# FY.net
KiCad netlist of a schematic drawn in EAGLE
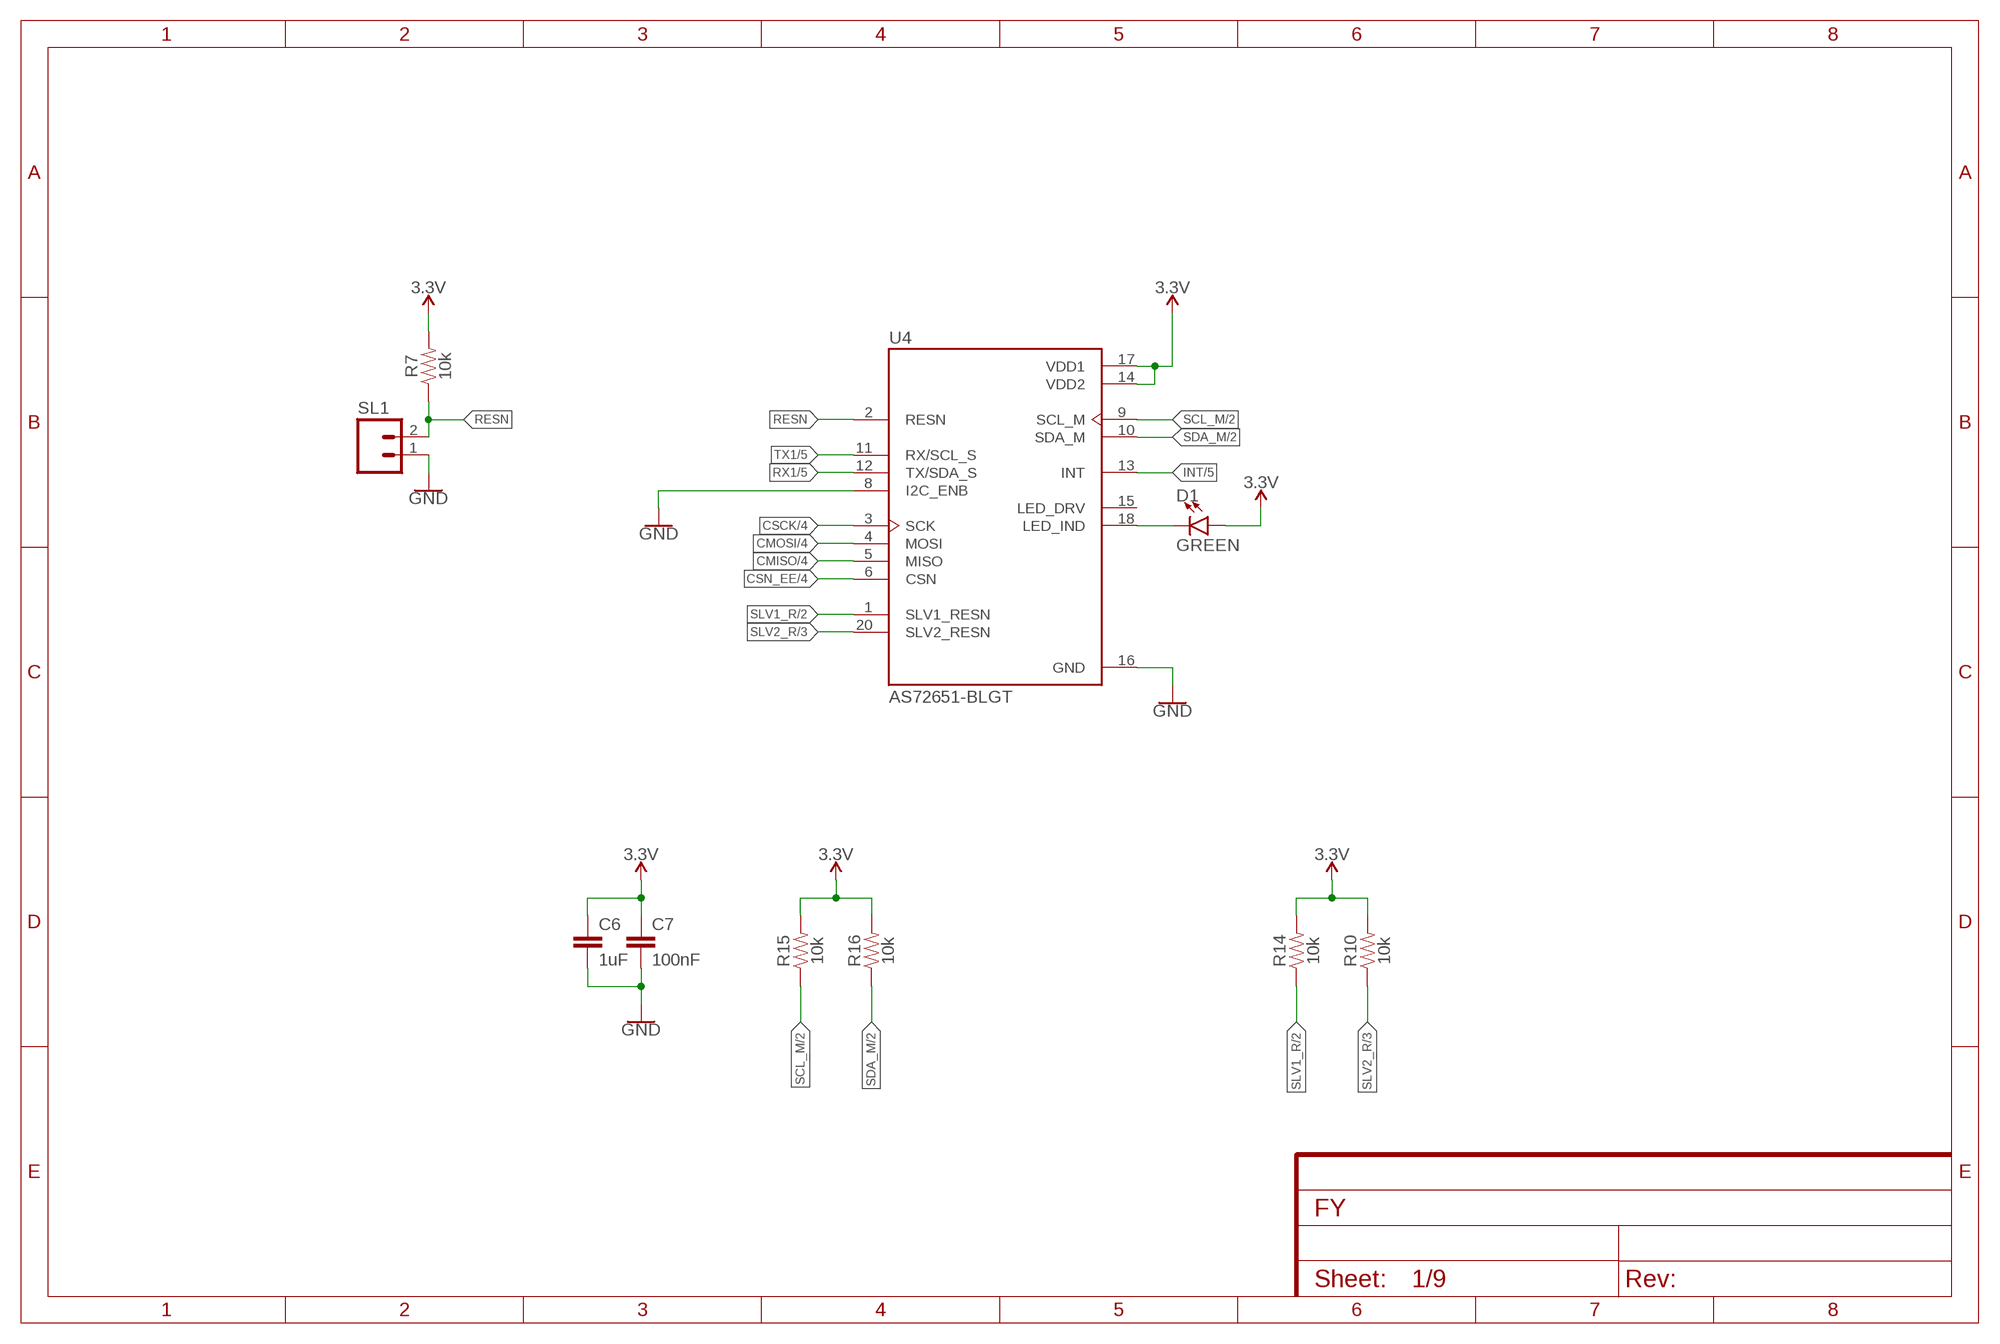
[diagram p0: schematic, sheet 1]
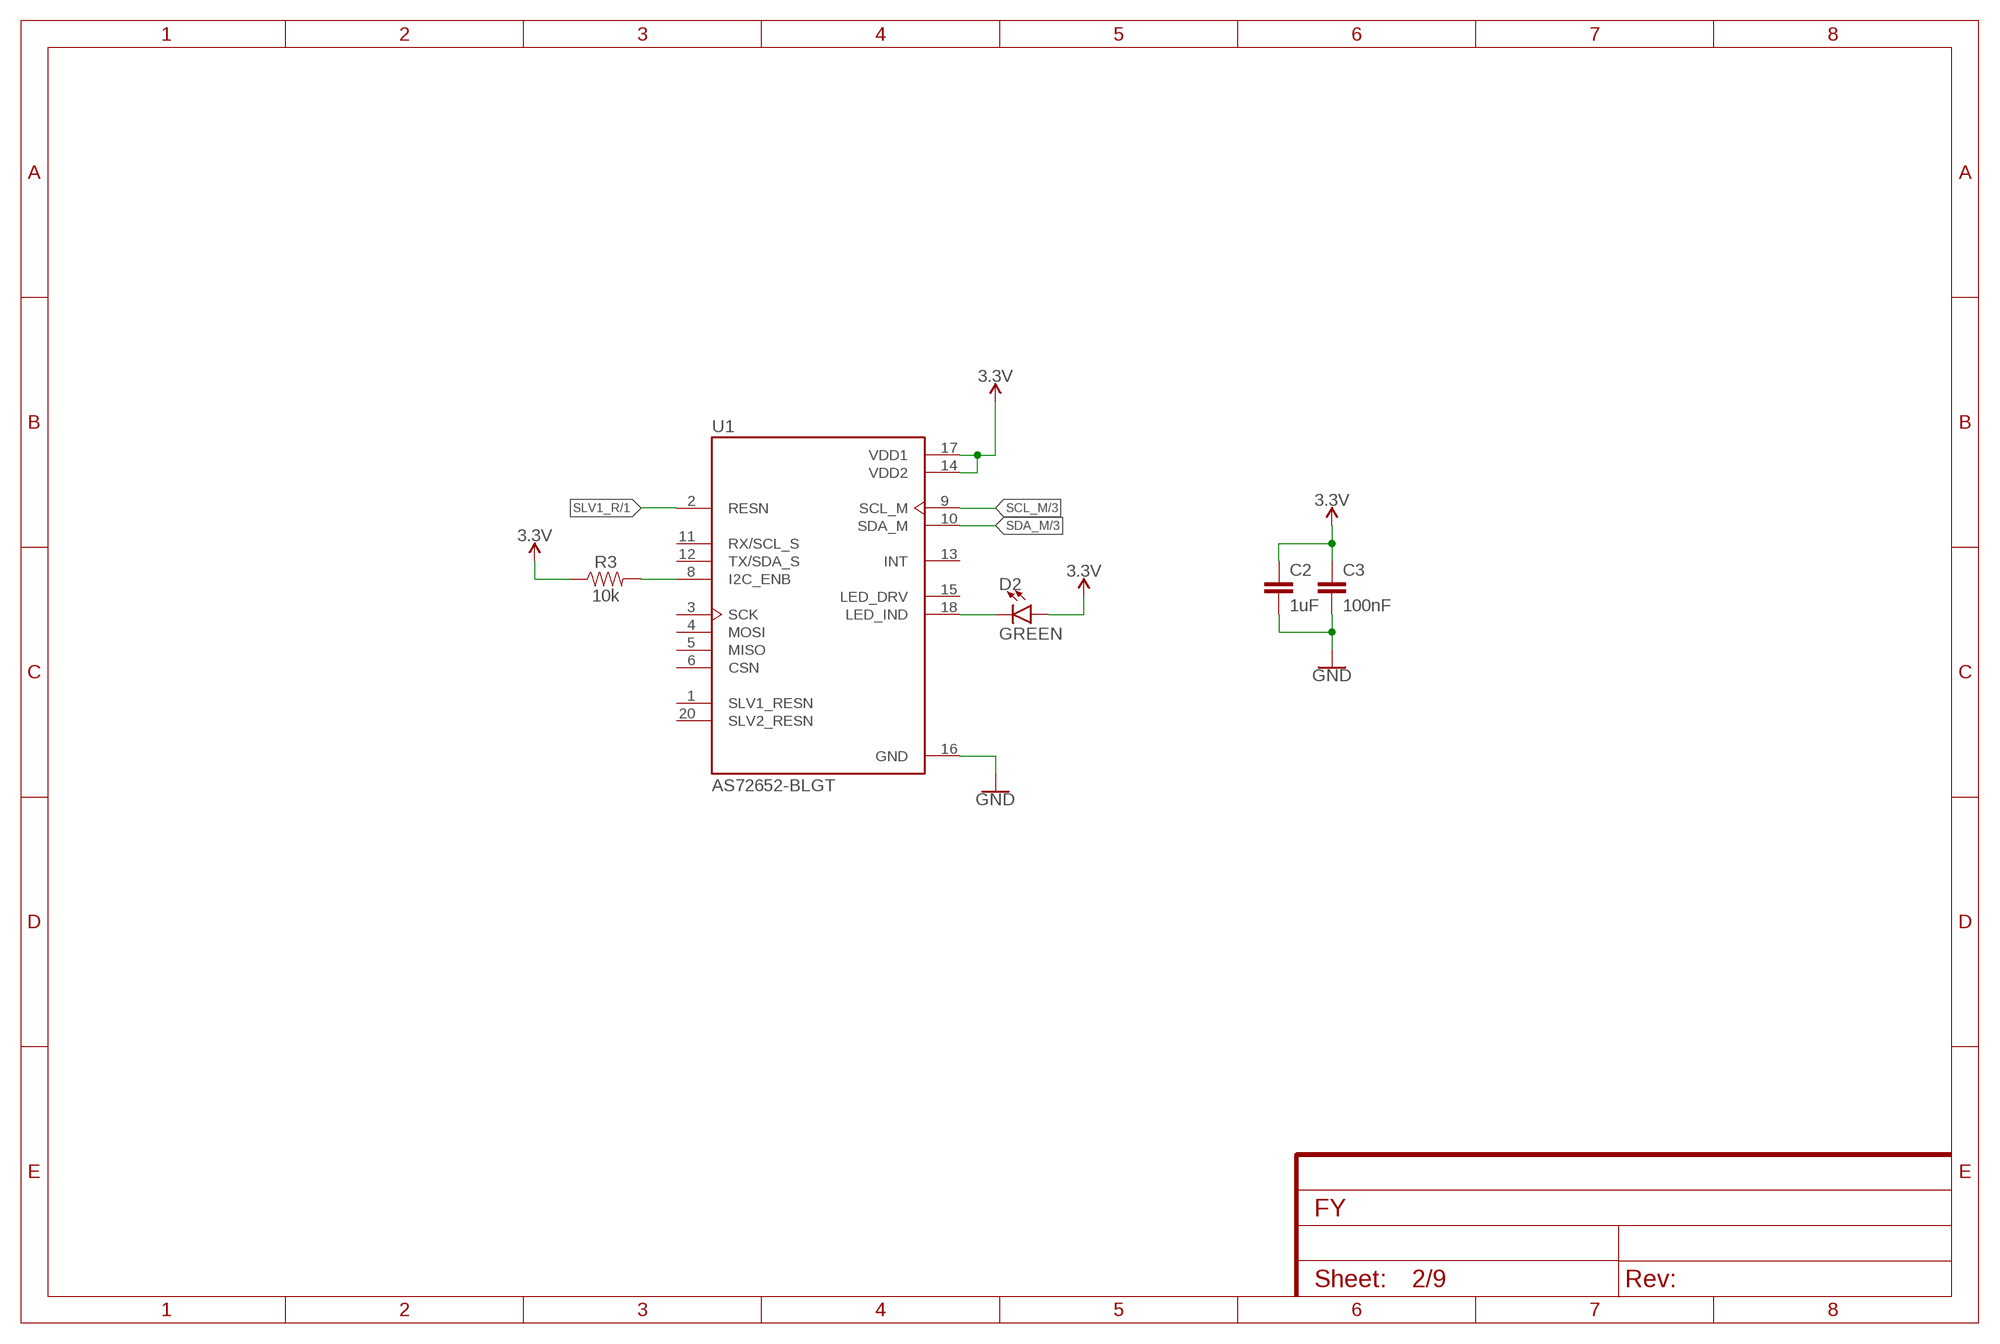
[diagram p1: schematic, sheet 2]
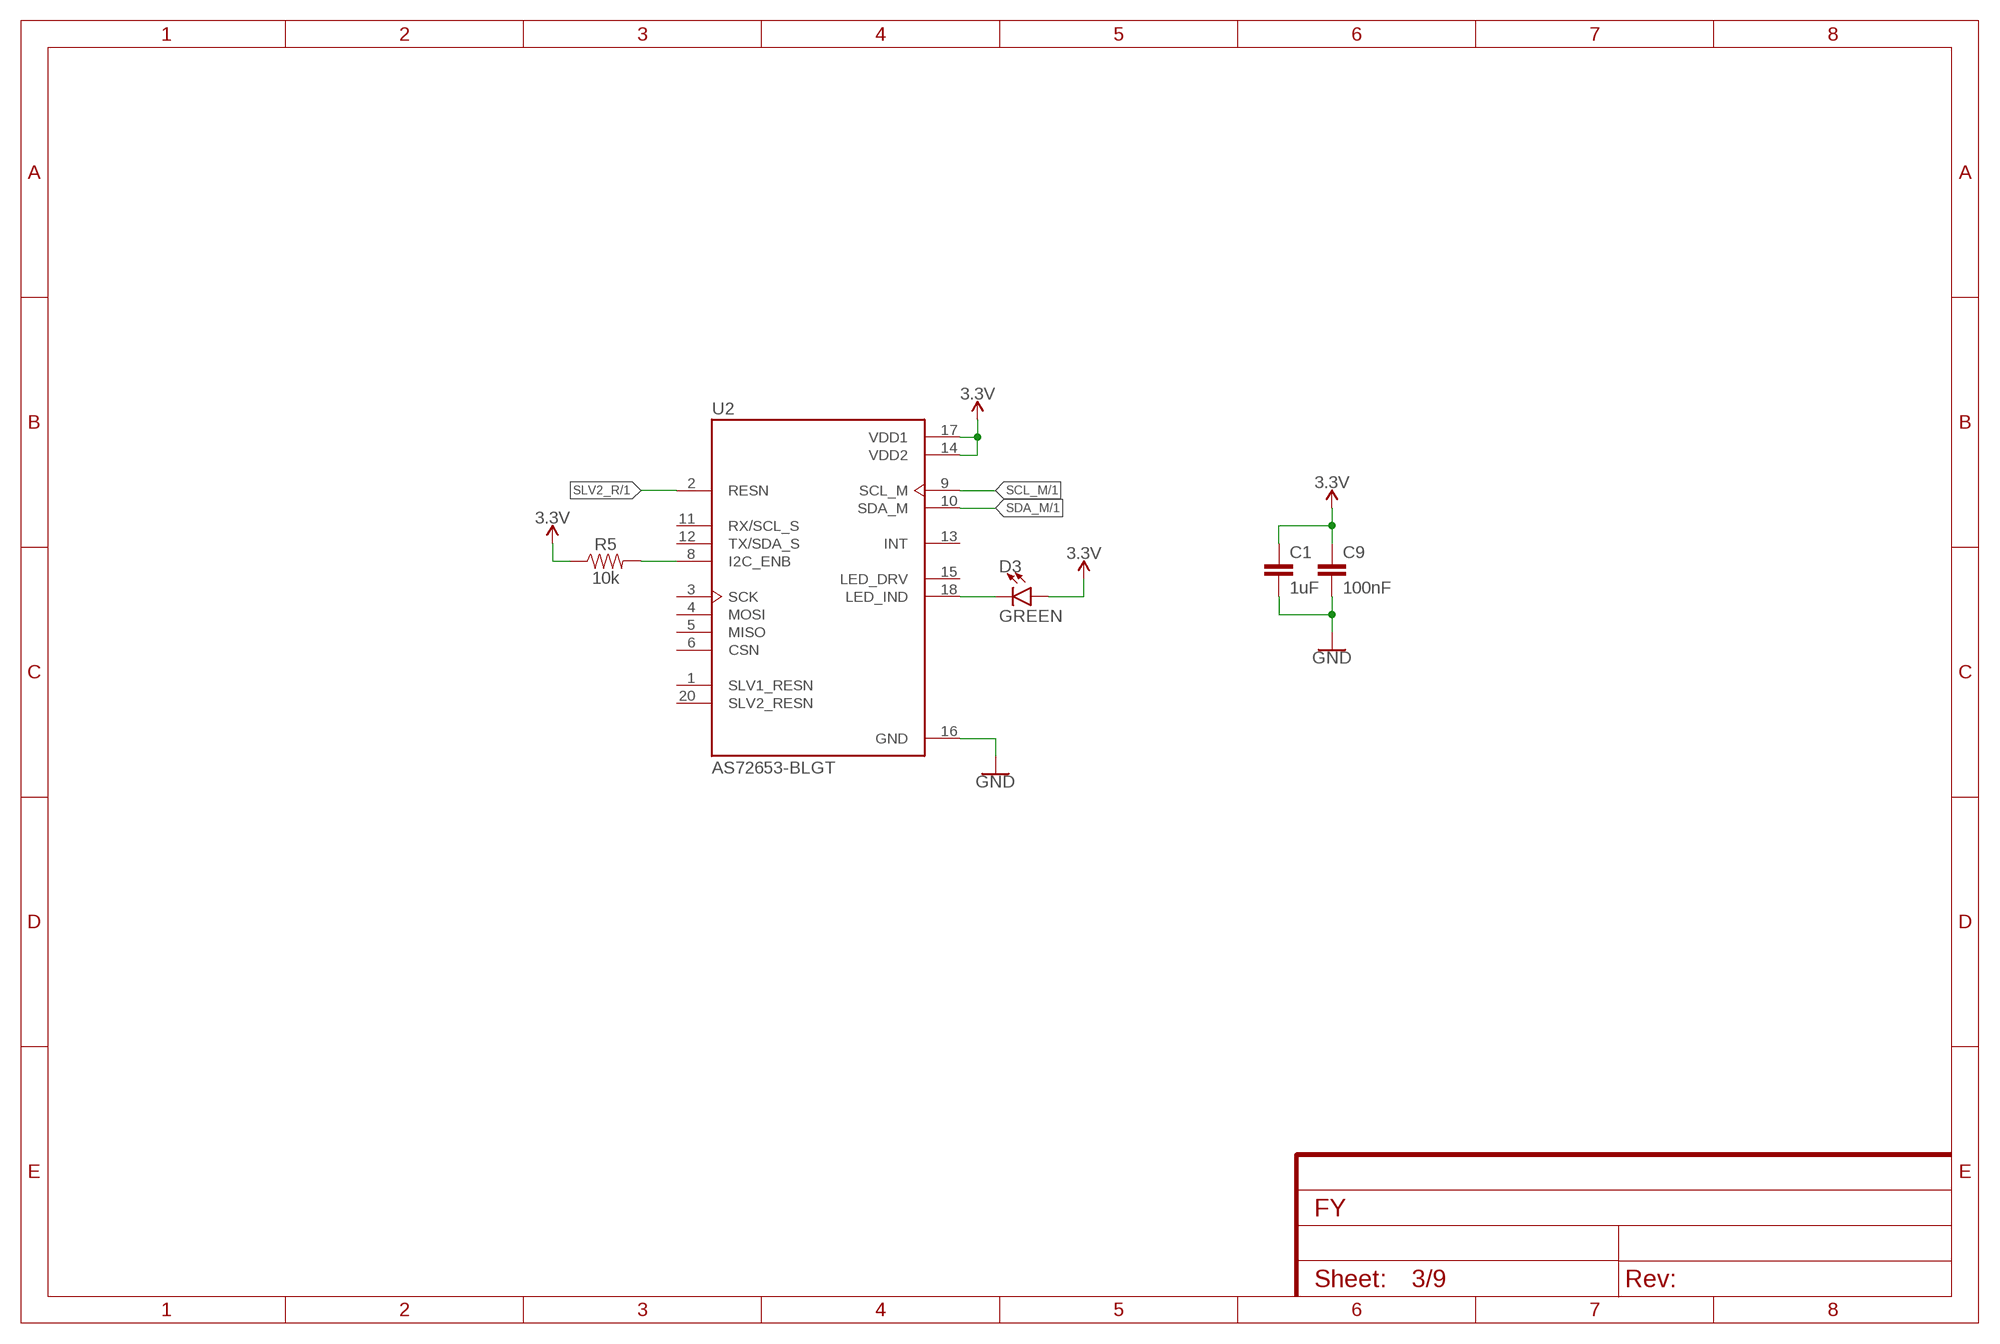
[diagram p2: schematic, sheet 3]
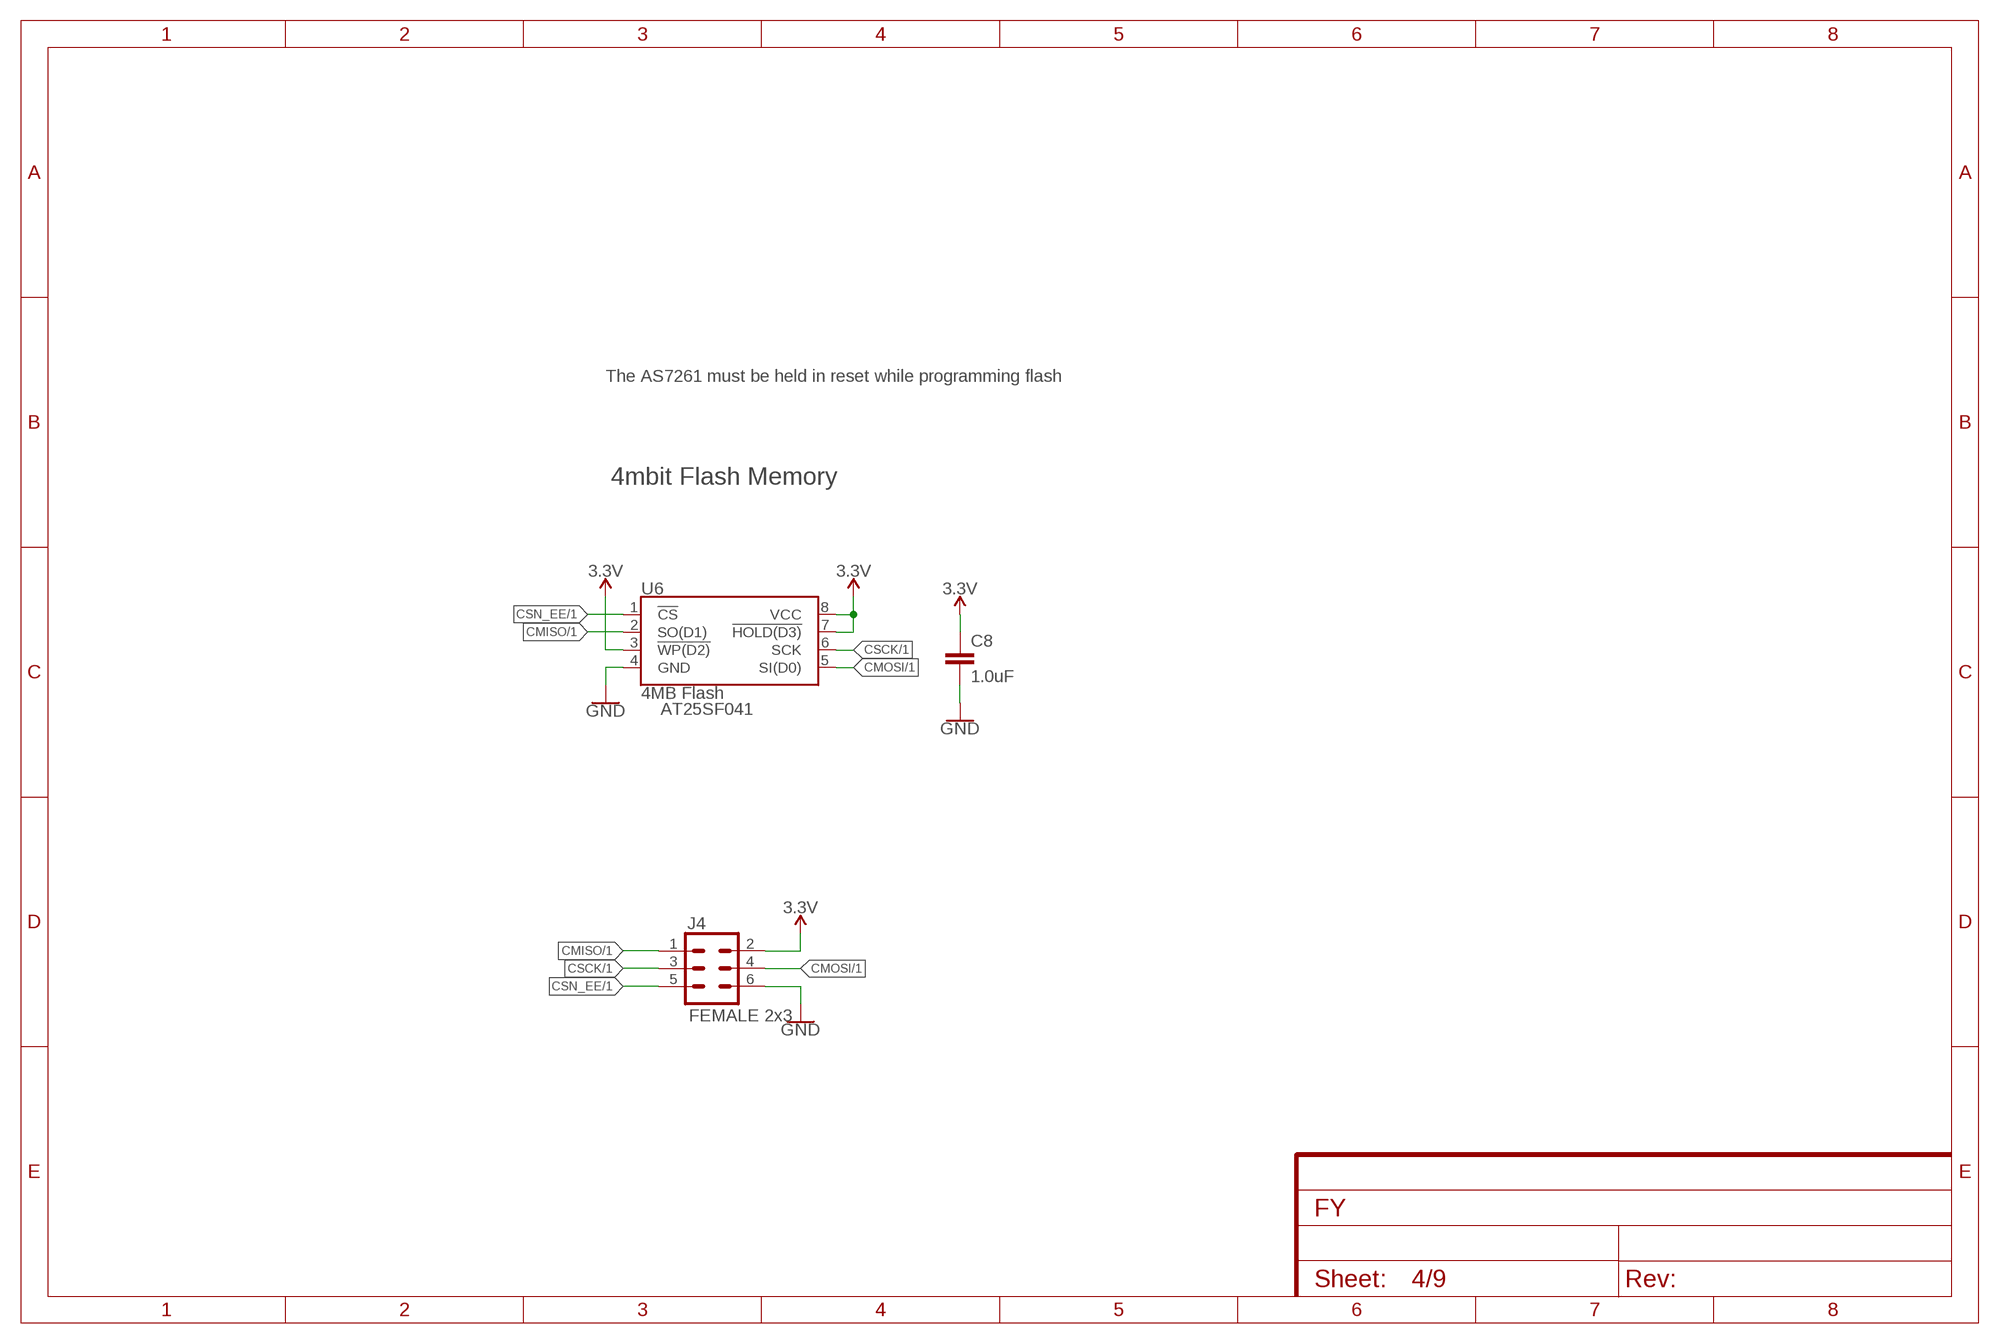
[diagram p3: schematic, sheet 4]
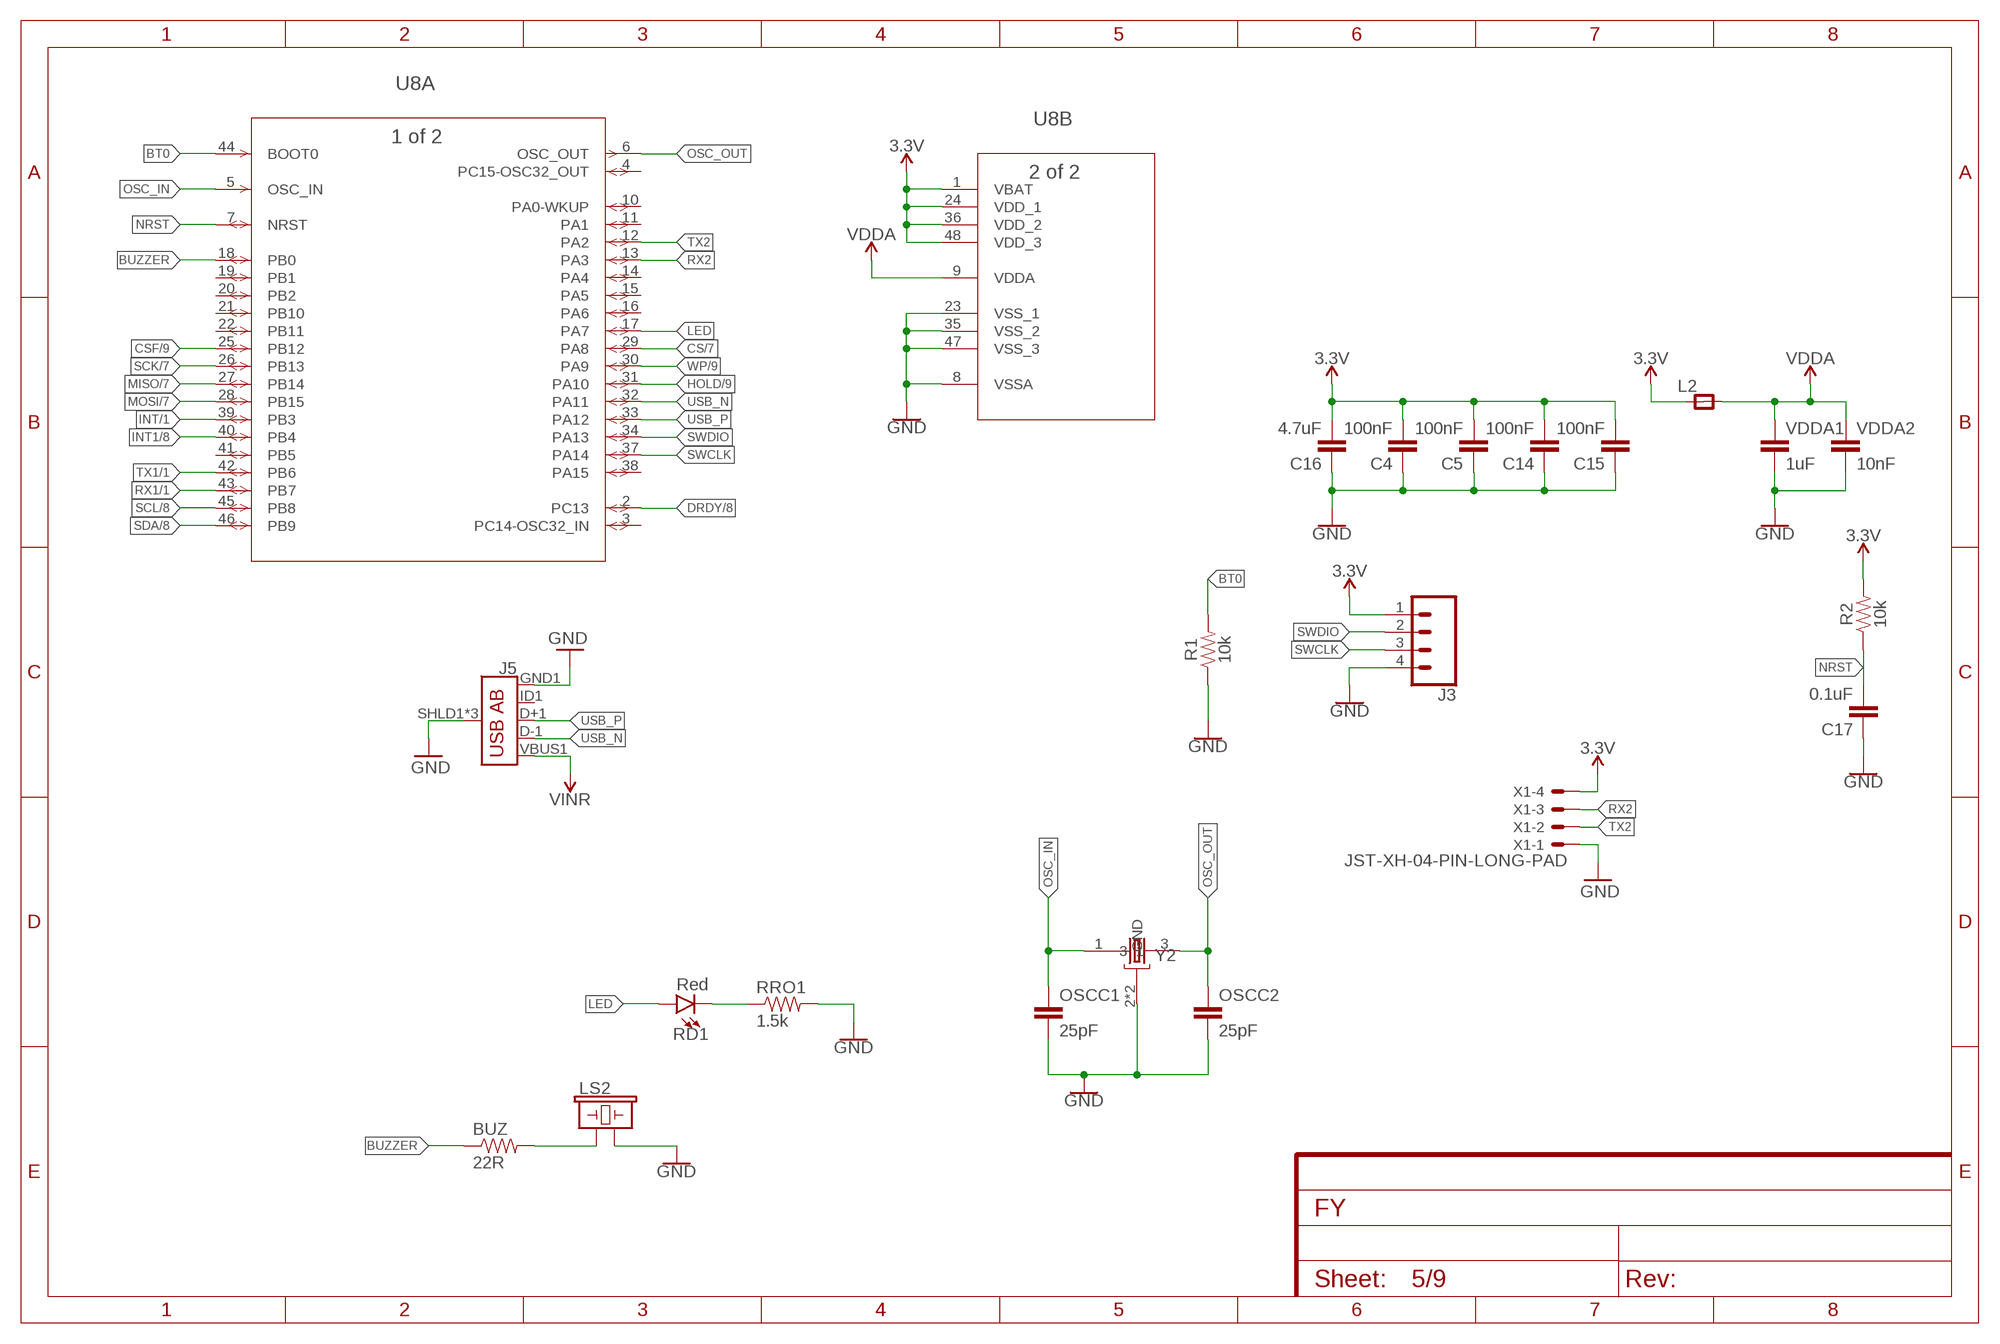
[diagram p4: schematic, sheet 5]
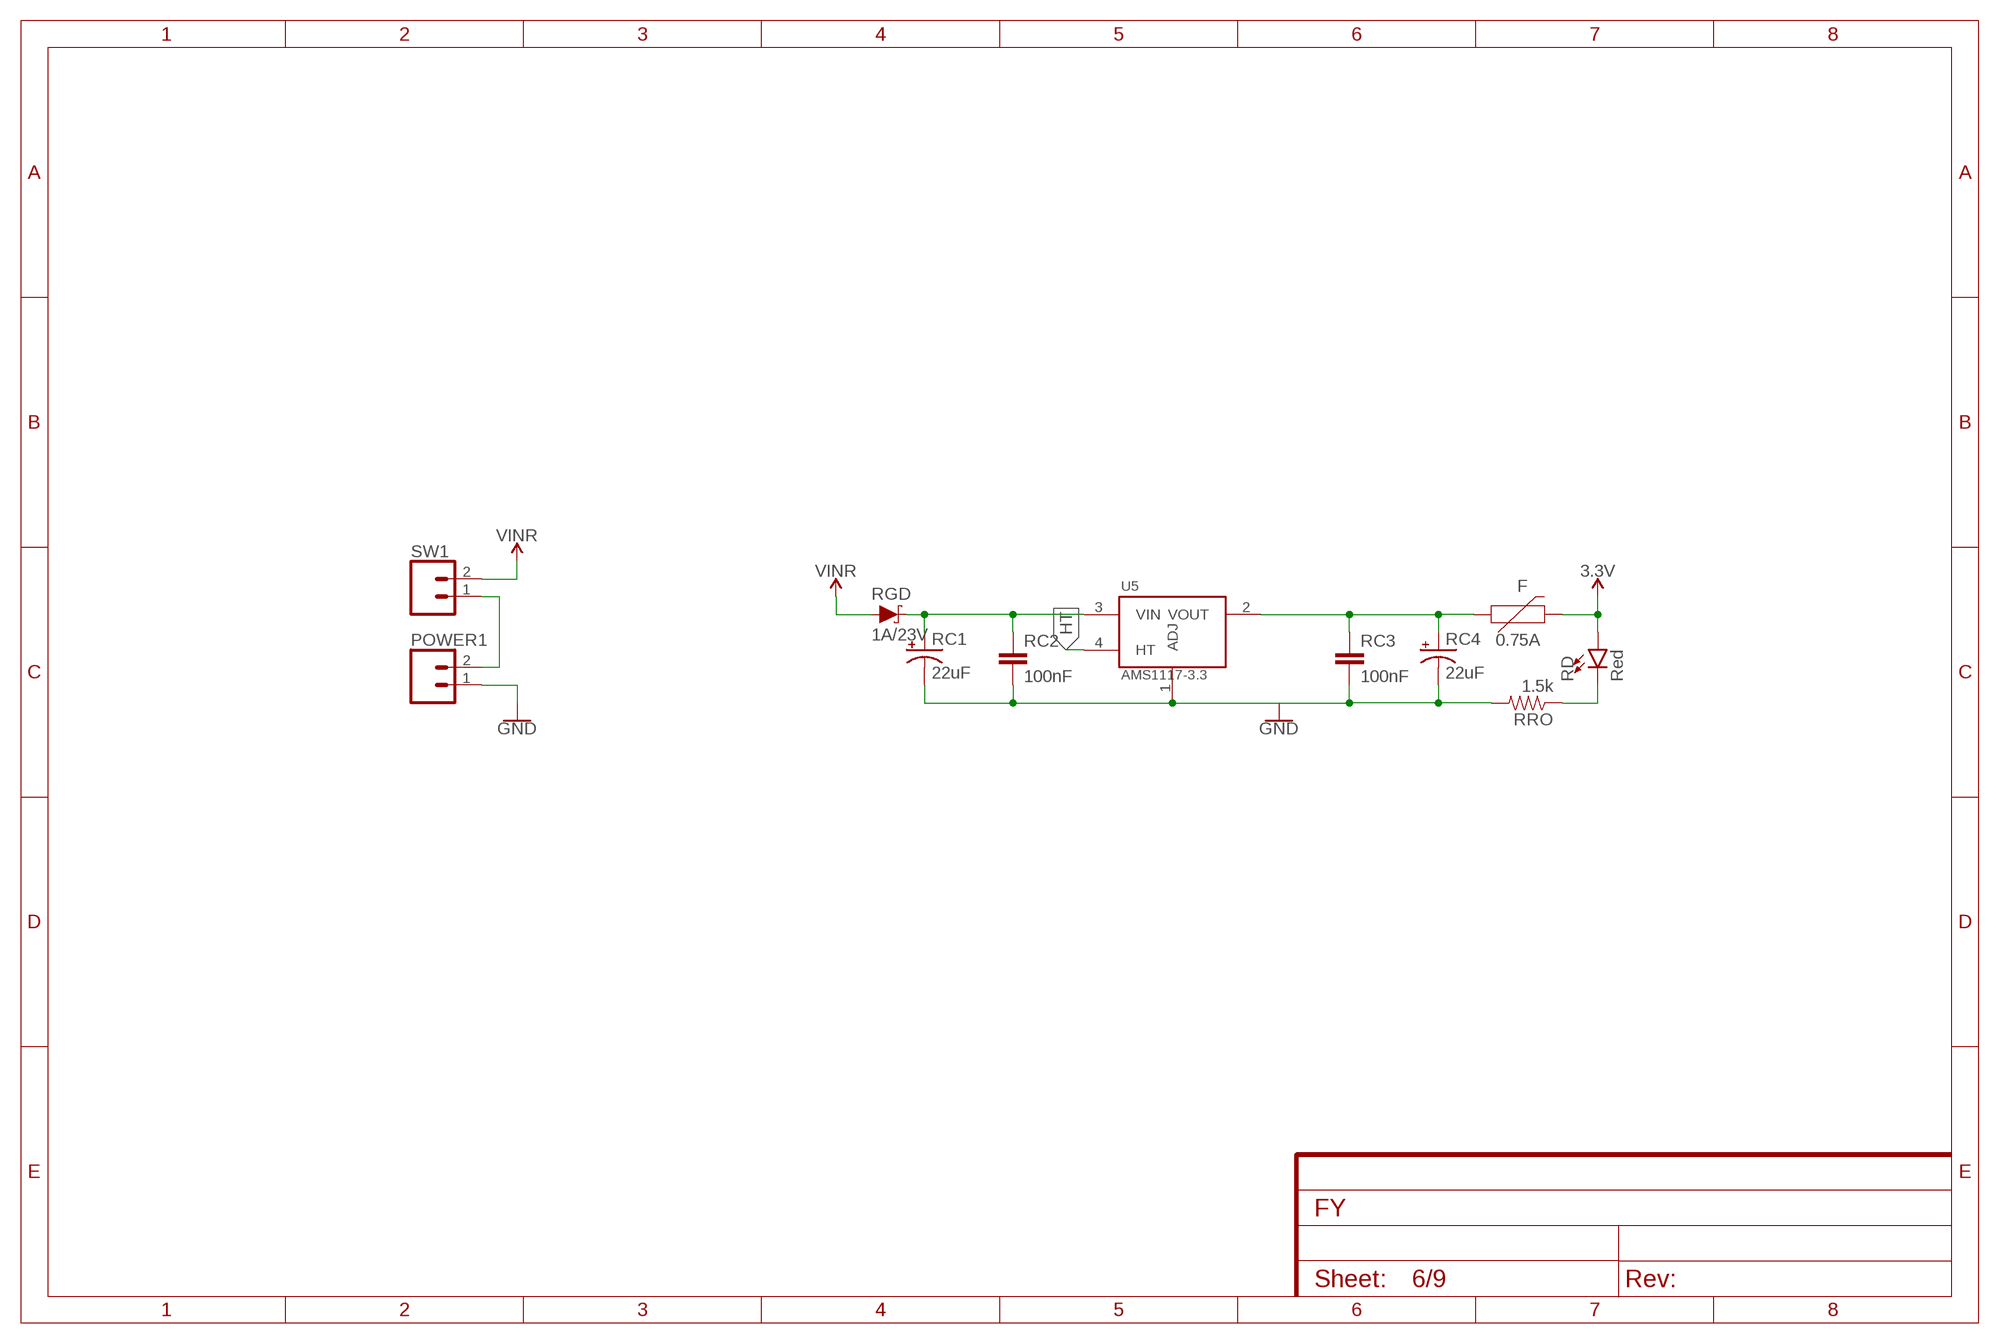
[diagram p5: schematic, sheet 6]
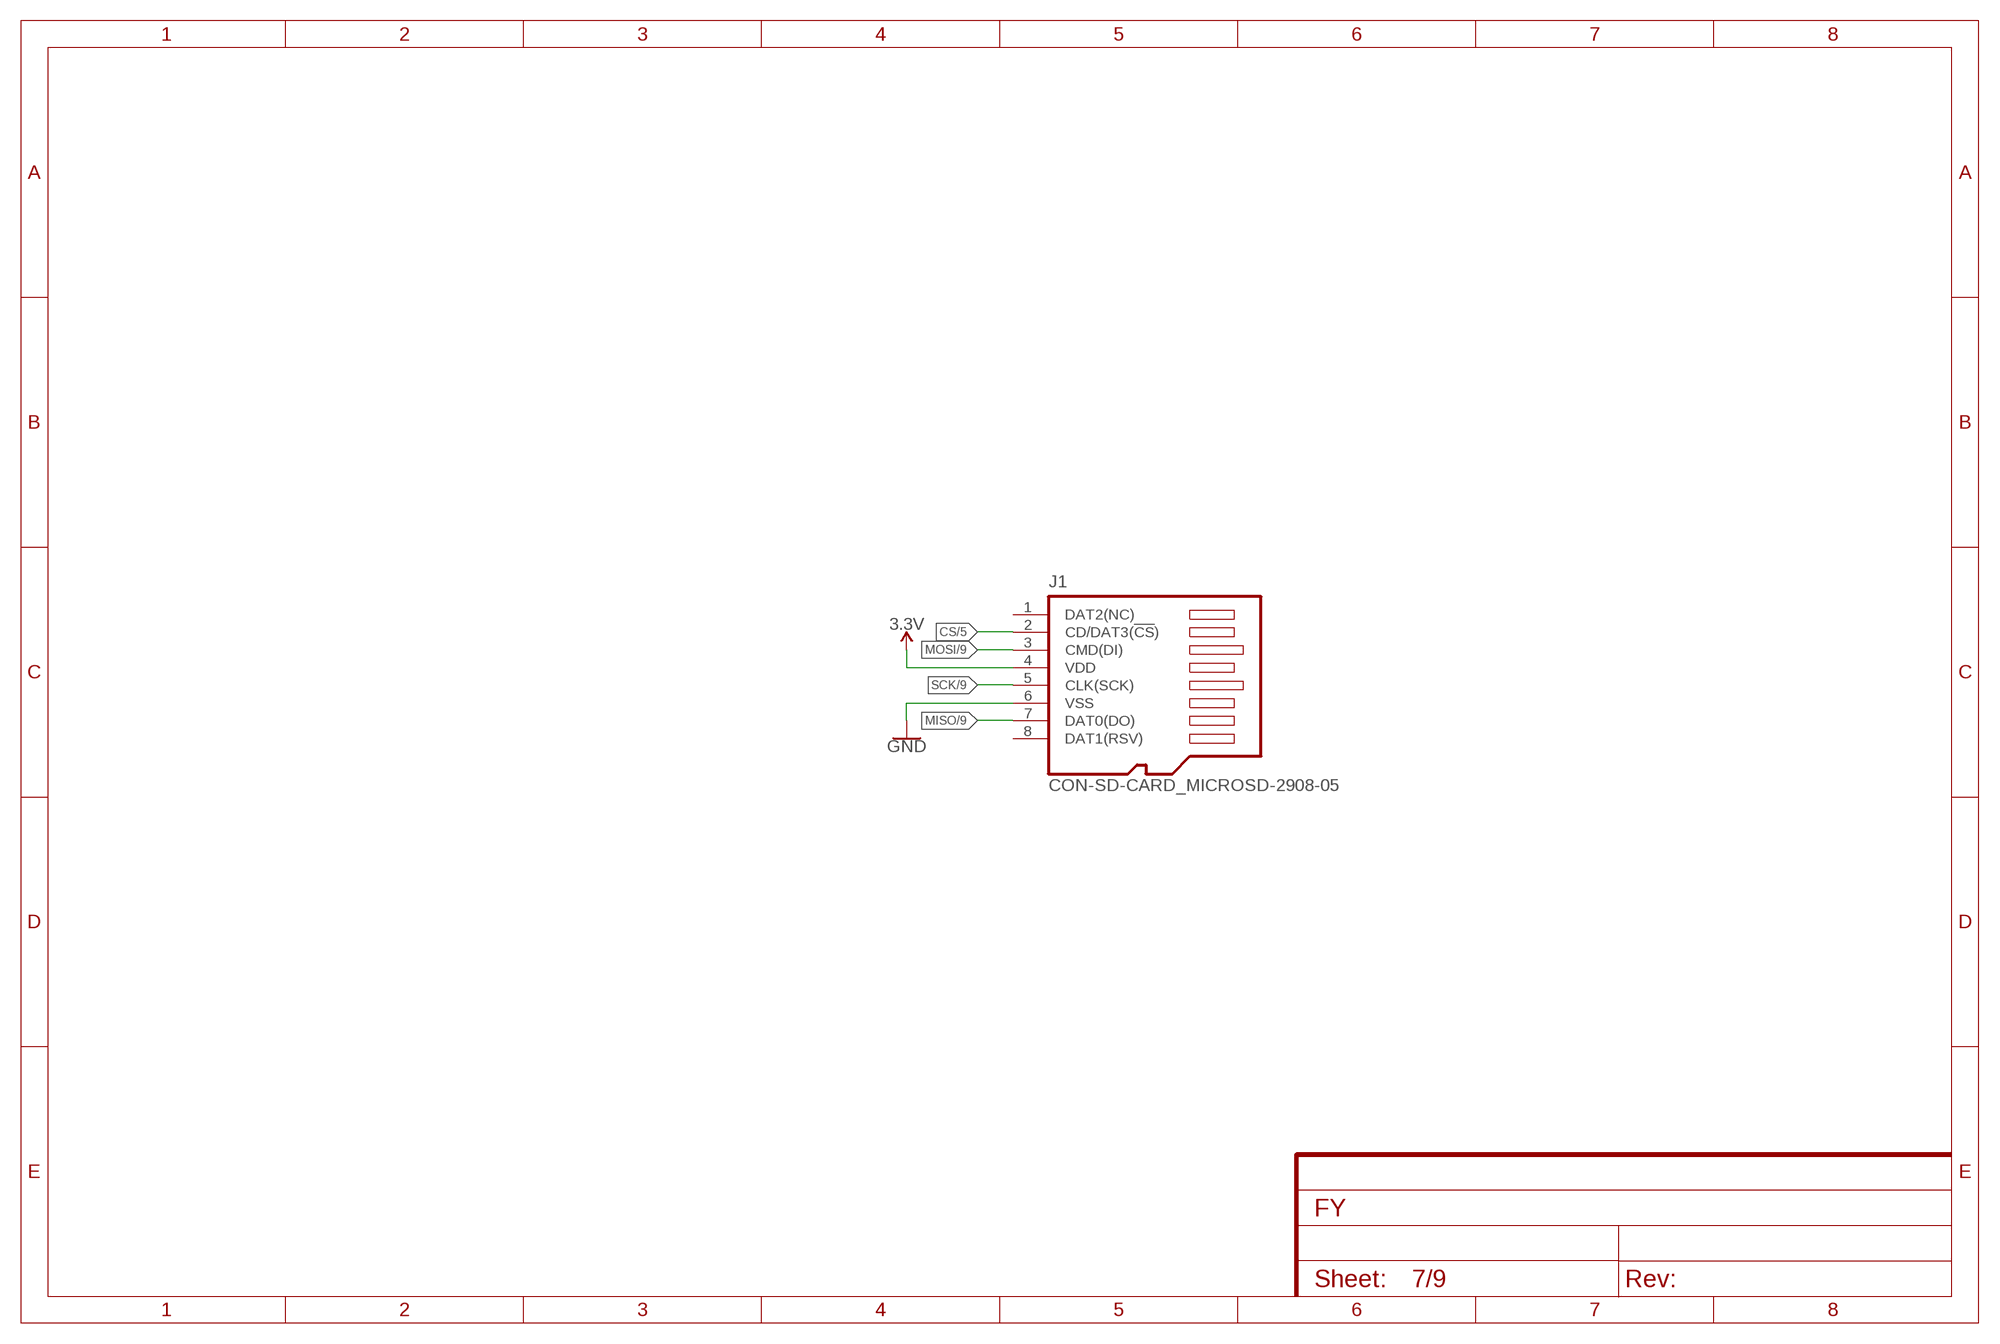
[diagram p6: schematic, sheet 7]
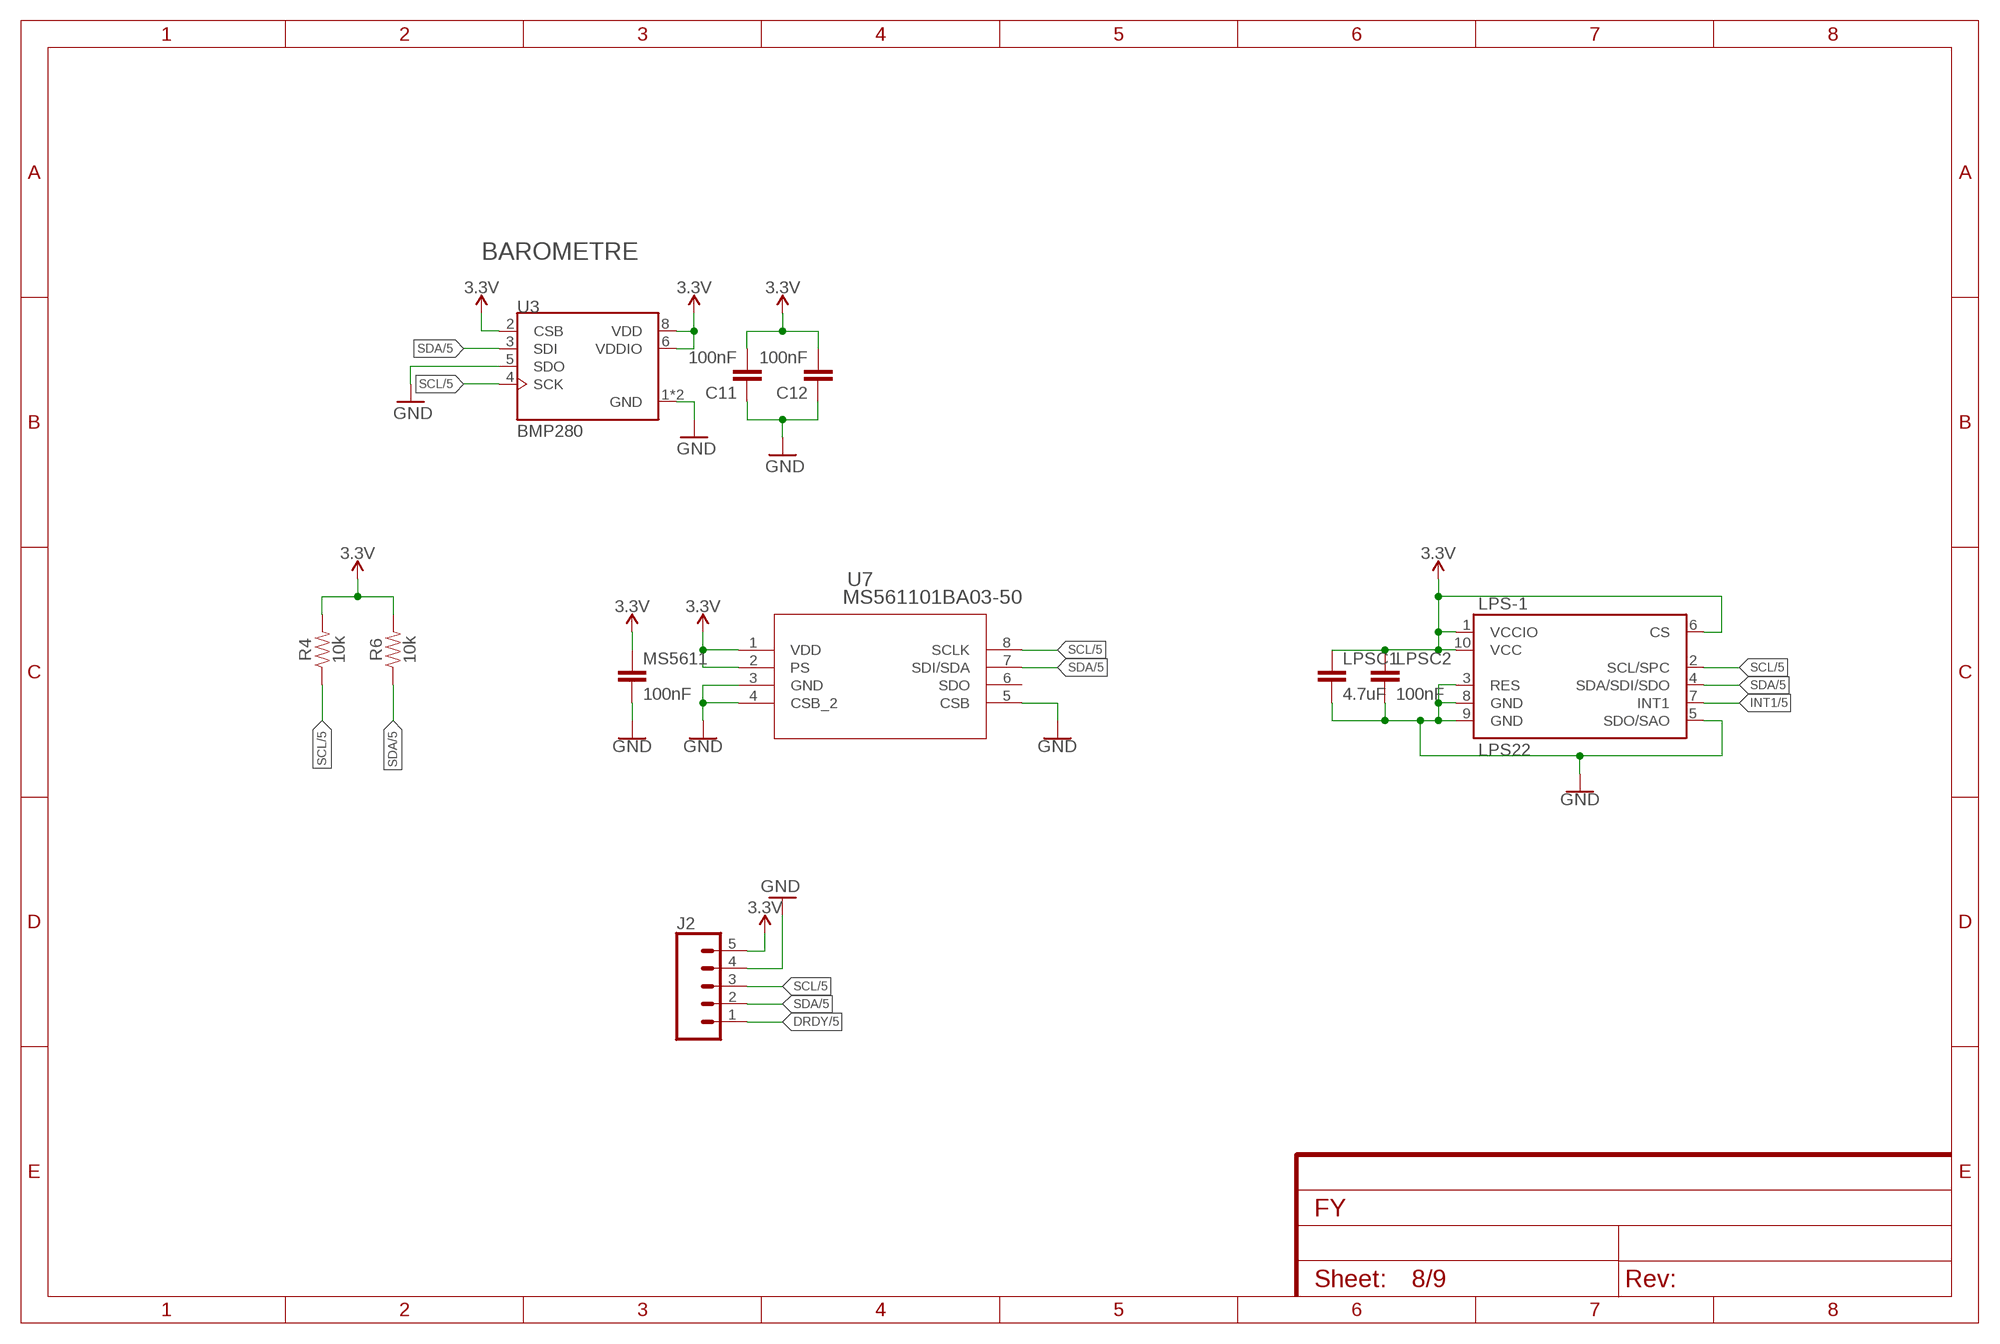
[diagram p7: schematic, sheet 8]
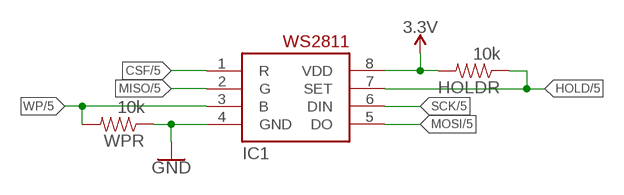
[diagram p8: schematic, sheet 9]

(export (version "E")
  (design (tool "Eeschema 10.0.6"))
  (components
    (comp (ref "C1")
      (value "1uF")
      (footprint "eagle-import:0603")
      (libsource (lib "eagle-import") (part "10UF-0603-6.3V-20%"))
    )
    (comp (ref "C9")
      (value "100nF")
      (footprint "eagle-import:0603")
      (libsource (lib "eagle-import") (part "0.1UF-0603-25V-(+80/-20%)"))
    )
    (comp (ref "D3")
      (value "GREEN")
      (footprint "eagle-import:LED-0603")
      (libsource (lib "eagle-import") (part "LED-GREEN0603"))
    )
    (comp (ref "R5")
      (value "10k")
      (footprint "eagle-import:0603")
      (libsource (lib "eagle-import") (part "0.05OHM-0603-1/5W-1%"))
    )
    (comp (ref "U2")
      (value "AS72653-BLGT")
      (footprint "eagle-import:PQFN65P470X450X270-20N")
      (fields (field (name "MF") "ams") (field (name "MP") "AS72651-BLGT"))
      (libsource (lib "eagle-import") (part "AS72651-BLGT"))
    )
    (comp (ref "C6")
      (value "1uF")
      (footprint "eagle-import:0603")
      (libsource (lib "eagle-import") (part "10UF-0603-6.3V-20%"))
    )
    (comp (ref "C7")
      (value "100nF")
      (footprint "eagle-import:0603")
      (libsource (lib "eagle-import") (part "0.1UF-0603-25V-(+80/-20%)"))
    )
    (comp (ref "D1")
      (value "GREEN")
      (footprint "eagle-import:LED-0603")
      (libsource (lib "eagle-import") (part "LED-GREEN0603"))
    )
    (comp (ref "R7")
      (value "10k")
      (footprint "eagle-import:0603")
      (libsource (lib "eagle-import") (part "10KOHM-0603-1/10W-1%"))
    )
    (comp (ref "R10")
      (value "10k")
      (footprint "eagle-import:0603")
      (libsource (lib "eagle-import") (part "10KOHM-0603-1/10W-1%"))
    )
    (comp (ref "R14")
      (value "10k")
      (footprint "eagle-import:0603")
      (libsource (lib "eagle-import") (part "10KOHM-0603-1/10W-1%"))
    )
    (comp (ref "R15")
      (value "10k")
      (footprint "eagle-import:0603")
      (libsource (lib "eagle-import") (part "10KOHM-0603-1/10W-1%"))
    )
    (comp (ref "R16")
      (value "10k")
      (footprint "eagle-import:0603")
      (libsource (lib "eagle-import") (part "10KOHM-0603-1/10W-1%"))
    )
    (comp (ref "SL1")
      (value "M02")
      (footprint "eagle-import:02P")
      (libsource (lib "eagle-import") (part "M02"))
    )
    (comp (ref "U4")
      (value "AS72651-BLGT")
      (footprint "eagle-import:PQFN65P470X450X270-20N")
      (fields (field (name "MF") "ams"))
      (libsource (lib "eagle-import") (part "AS72651-BLGT"))
    )
    (comp (ref "C11")
      (value "100nF")
      (footprint "eagle-import:0603")
      (libsource (lib "eagle-import") (part "SparkFun-Capacitors_510_1.0UF-0603-16V-10%"))
    )
    (comp (ref "C12")
      (value "100nF")
      (footprint "eagle-import:0603")
      (libsource (lib "eagle-import") (part "SparkFun-Capacitors_510_1.0UF-0603-16V-10%"))
    )
    (comp (ref "J2")
      (value "CONN_05LOCK_LONGPADS")
      (footprint "eagle-import:1X05_LOCK_LONGPADS")
      (libsource (lib "eagle-import") (part "CONN_05LOCK_LONGPADS"))
    )
    (comp (ref "LPS-1")
      (value "LPS22")
      (footprint "eagle-import:LPS22H")
      (fields (field (name "MANUFACTURER") "ST"))
      (libsource (lib "eagle-import") (part "LPS2XH-22"))
    )
    (comp (ref "LPSC1")
      (value "4.7uF")
      (footprint "eagle-import:0603")
      (libsource (lib "eagle-import") (part "SparkFun-Capacitors_510_0.1UF-0603-25V-(+80/-20%)"))
    )
    (comp (ref "LPSC2")
      (value "100nF")
      (footprint "eagle-import:0603")
      (libsource (lib "eagle-import") (part "SparkFun-Capacitors_510_0.1UF-0603-25V-(+80/-20%)"))
    )
    (comp (ref "MS5611")
      (value "100nF")
      (footprint "eagle-import:0603")
      (libsource (lib "eagle-import") (part "SparkFun-Capacitors_510_0.1UF-0603-25V-(+80/-20%)"))
    )
    (comp (ref "R4")
      (value "10k")
      (footprint "eagle-import:0603")
      (libsource (lib "eagle-import") (part "10KOHM-0603-1/10W-1%"))
    )
    (comp (ref "R6")
      (value "10k")
      (footprint "eagle-import:0603")
      (libsource (lib "eagle-import") (part "10KOHM-0603-1/10W-1%"))
    )
    (comp (ref "U3")
      (value "BMP280")
      (footprint "eagle-import:XDCR_BMP280")
      (fields (field (name "MF") "Bosch"))
      (libsource (lib "eagle-import") (part "BMP280"))
    )
    (comp (ref "U7")
      (value "MS561101BA03-50")
      (footprint "eagle-import:SON8_MS5611_TEC")
      (fields (field (name "COPYRIGHT") "Copyright (C) 2016 Accelerated Designs. All rights reserved"))
      (libsource (lib "eagle-import") (part "MS561101BA03-50"))
    )
    (comp (ref "BUZ")
      (value "22R")
      (footprint "eagle-import:0603-RES")
      (libsource (lib "eagle-import") (part "2.0KOHM1/10W5%(0603)"))
    )
    (comp (ref "C4")
      (value "100nF")
      (footprint "eagle-import:0603")
      (libsource (lib "eagle-import") (part "22PF-0603-50V-5%"))
    )
    (comp (ref "C5")
      (value "100nF")
      (footprint "eagle-import:0603")
      (libsource (lib "eagle-import") (part "22PF-0603-50V-5%"))
    )
    (comp (ref "C14")
      (value "100nF")
      (footprint "eagle-import:0603")
      (libsource (lib "eagle-import") (part "22PF-0603-50V-5%"))
    )
    (comp (ref "C15")
      (value "100nF")
      (footprint "eagle-import:0603")
      (libsource (lib "eagle-import") (part "22PF-0603-50V-5%"))
    )
    (comp (ref "C16")
      (value "4.7uF")
      (footprint "eagle-import:0603")
      (libsource (lib "eagle-import") (part "22PF-0603-50V-5%"))
    )
    (comp (ref "C17")
      (value "0.1uF")
      (footprint "eagle-import:0603")
      (libsource (lib "eagle-import") (part "22PF-0603-50V-5%"))
    )
    (comp (ref "J3")
      (value "CONN_04")
      (footprint "eagle-import:1X04")
      (libsource (lib "eagle-import") (part "CONN_04"))
    )
    (comp (ref "J5")
      (value "USB_AB_SMT")
      (footprint "eagle-import:USB-AB-MICRO-SMD")
      (libsource (lib "eagle-import") (part "USB_AB_SMT"))
    )
    (comp (ref "L2")
      (value "RC-MASTER-SMD_FB_0805MP")
      (footprint "eagle-import:RC-MASTER-SMD_L0805MP")
      (libsource (lib "eagle-import") (part "RC-MASTER-SMD_FB_0805MP"))
    )
    (comp (ref "LS2")
      (value "BUZZER-PTH")
      (footprint "eagle-import:BUZZER-12MM")
      (libsource (lib "eagle-import") (part "BUZZER-PTH"))
    )
    (comp (ref "OSCC1")
      (value "25pF")
      (footprint "eagle-import:0603")
      (libsource (lib "eagle-import") (part "SparkFun-Capacitors_510_0.1UF-0603-25V-(+80/-20%)"))
    )
    (comp (ref "OSCC2")
      (value "25pF")
      (footprint "eagle-import:0603")
      (libsource (lib "eagle-import") (part "SparkFun-Capacitors_510_0.1UF-0603-25V-(+80/-20%)"))
    )
    (comp (ref "R1")
      (value "10k")
      (footprint "eagle-import:0603")
      (libsource (lib "eagle-import") (part "0.05OHM-0603-1/5W-1%"))
    )
    (comp (ref "R2")
      (value "10k")
      (footprint "eagle-import:0603")
      (libsource (lib "eagle-import") (part "0.05OHM-0603-1/5W-1%"))
    )
    (comp (ref "RD1")
      (value "Red")
      (footprint "eagle-import:LED-0603")
      (libsource (lib "eagle-import") (part "LED-RED0603-SMART"))
    )
    (comp (ref "RRO1")
      (value "1.5k")
      (footprint "eagle-import:0603-RES")
      (libsource (lib "eagle-import") (part "2.0KOHM1/10W5%(0603)"))
    )
    (comp (ref "U8")
      (value "STM32F103C8T6")
      (footprint "eagle-import:LQFP48-7X7MM")
      (fields (field (name "COPYRIGHT") "Copyright (C) 2018 Accelerated Designs. All rights reserved"))
      (libsource (lib "eagle-import") (part "STM32F103C8T6"))
    )
    (comp (ref "VDDA1")
      (value "1uF")
      (footprint "eagle-import:0603")
      (libsource (lib "eagle-import") (part "SparkFun-Capacitors_510_0.1UF-0603-25V-(+80/-20%)"))
    )
    (comp (ref "VDDA2")
      (value "10nF")
      (footprint "eagle-import:0603")
      (libsource (lib "eagle-import") (part "SparkFun-Capacitors_510_0.1UF-0603-25V-(+80/-20%)"))
    )
    (comp (ref "X1")
      (value "JST-XH-04-PIN-LONG-PAD")
      (footprint "eagle-import:JST-XH-04-PACKAGE-LONG-PAD")
      (libsource (lib "eagle-import") (part "JST-XH-04-PIN-LONG-PAD"))
    )
    (comp (ref "Y2")
      (value "ABM2B-8.000MHZ-10-1-U-T")
      (footprint "eagle-import:OSCCC500X320X110-4N")
      (fields (field (name "MF") "Abracon") (field (name "MP") "ABM3B-26.000MHZ-10-1-U-T"))
      (libsource (lib "eagle-import") (part "ABM3B-26.000MHZ-10-1-U-T"))
    )
    (comp (ref "C8")
      (value "1.0uF")
      (footprint "eagle-import:0603")
      (libsource (lib "eagle-import") (part "1.0UF-0603-16V-10%"))
    )
    (comp (ref "J4")
      (value "FEMALE 2x3")
      (footprint "eagle-import:2X3")
      (libsource (lib "eagle-import") (part "CONN_03X2FEMALE"))
    )
    (comp (ref "U6")
      (value "4MB Flash")
      (footprint "eagle-import:SO08")
      (libsource (lib "eagle-import") (part "AT25SF041"))
    )
    (comp (ref "C2")
      (value "1uF")
      (footprint "eagle-import:0603")
      (libsource (lib "eagle-import") (part "10UF-0603-6.3V-20%"))
    )
    (comp (ref "C3")
      (value "100nF")
      (footprint "eagle-import:0603")
      (libsource (lib "eagle-import") (part "0.1UF-0603-25V-(+80/-20%)"))
    )
    (comp (ref "D2")
      (value "GREEN")
      (footprint "eagle-import:LED-0603")
      (libsource (lib "eagle-import") (part "LED-GREEN0603"))
    )
    (comp (ref "R3")
      (value "10k")
      (footprint "eagle-import:0603")
      (libsource (lib "eagle-import") (part "0.05OHM-0603-1/5W-1%"))
    )
    (comp (ref "U1")
      (value "AS72652-BLGT")
      (footprint "eagle-import:PQFN65P470X450X270-20N")
      (fields (field (name "MF") "ams") (field (name "MP") "AS72651-BLGT"))
      (libsource (lib "eagle-import") (part "AS72651-BLGT"))
    )
    (comp (ref "F")
      (value "0.75A")
      (footprint "eagle-import:1206")
      (libsource (lib "eagle-import") (part "PPTC_THREE-QUARTER-AMP"))
    )
    (comp (ref "POWER1")
      (value "CONN_023.5MM-NO_SILK")
      (footprint "eagle-import:SCREWTERMINAL-3.5MM-2-NS")
      (libsource (lib "eagle-import") (part "CONN_023.5MM-NO_SILK"))
    )
    (comp (ref "RC1")
      (value "22uF")
      (footprint "eagle-import:EIA3528")
      (libsource (lib "eagle-import") (part "10UF-POLAR-EIA3528-20V-10%(TANT)"))
    )
    (comp (ref "RC2")
      (value "100nF")
      (footprint "eagle-import:0603")
      (libsource (lib "eagle-import") (part "SparkFun-Capacitors_510_0.1UF-0603-25V-(+80/-20%)"))
    )
    (comp (ref "RC3")
      (value "100nF")
      (footprint "eagle-import:0603")
      (libsource (lib "eagle-import") (part "SparkFun-Capacitors_510_0.1UF-0603-25V-(+80/-20%)"))
    )
    (comp (ref "RC4")
      (value "22uF")
      (footprint "eagle-import:EIA3528")
      (libsource (lib "eagle-import") (part "10UF-POLAR-EIA3528-20V-10%(TANT)"))
    )
    (comp (ref "RD")
      (value "Red")
      (footprint "eagle-import:LED-0603")
      (libsource (lib "eagle-import") (part "LED-RED0603-SMART"))
    )
    (comp (ref "RGD")
      (value "1A/23V")
      (footprint "eagle-import:SOD-323")
      (libsource (lib "eagle-import") (part "DIODE-SCHOTTKY-BAT20J"))
    )
    (comp (ref "RRO")
      (value "1.5k")
      (footprint "eagle-import:0603-RES")
      (libsource (lib "eagle-import") (part "2.0KOHM1/10W5%(0603)"))
    )
    (comp (ref "SW1")
      (value "CONN_023.5MM-NO_SILK")
      (footprint "eagle-import:SCREWTERMINAL-3.5MM-2-NS")
      (libsource (lib "eagle-import") (part "CONN_023.5MM-NO_SILK"))
    )
    (comp (ref "U5")
      (value "AMS1117-3.3")
      (footprint "eagle-import:SOT229P700X180-4N")
      (fields (field (name "MF") "Advanced Monolithic Systems"))
      (libsource (lib "eagle-import") (part "AMS1117-3.3"))
    )
    (comp (ref "HOLDR")
      (value "10k")
      (footprint "eagle-import:0603-RES")
      (libsource (lib "eagle-import") (part "2.0KOHM1/10W5%(0603)"))
    )
    (comp (ref "IC1")
      (value "EN25F40-100GCP-TR")
      (footprint "eagle-import:SO08-SKINNYPADS")
      (libsource (lib "eagle-import") (part "WS2811-SOP8"))
    )
    (comp (ref "WPR")
      (value "10k")
      (footprint "eagle-import:0603-RES")
      (libsource (lib "eagle-import") (part "2.0KOHM1/10W5%(0603)"))
    )
    (comp (ref "J1")
      (value "CON-SD-CARD_MICROSD-2908-05")
      (footprint "eagle-import:CON-SD-CARD_2908-05")
      (libsource (lib "eagle-import") (part "CON-SD-CARD_MICROSD-2908-05"))
    )
  )
  (nets
    (net (code "1") (name "3.3V") (class "Default")
      (node (ref "C1") (pin "1") (pinfunction "1_1") (pintype "passive"))
      (node (ref "C11") (pin "2") (pinfunction "2_2") (pintype "passive"))
      (node (ref "C12") (pin "2") (pinfunction "2_2") (pintype "passive"))
      (node (ref "C14") (pin "2") (pinfunction "2_2") (pintype "passive"))
      (node (ref "C15") (pin "2") (pinfunction "2_2") (pintype "passive"))
      (node (ref "C16") (pin "2") (pinfunction "2_2") (pintype "passive"))
      (node (ref "C2") (pin "1") (pinfunction "1_1") (pintype "passive"))
      (node (ref "C3") (pin "1") (pinfunction "1_1") (pintype "passive"))
      (node (ref "C4") (pin "2") (pinfunction "2_2") (pintype "passive"))
      (node (ref "C5") (pin "2") (pinfunction "2_2") (pintype "passive"))
      (node (ref "C6") (pin "1") (pinfunction "1_1") (pintype "passive"))
      (node (ref "C7") (pin "1") (pinfunction "1_1") (pintype "passive"))
      (node (ref "C8") (pin "1") (pinfunction "1_1") (pintype "passive"))
      (node (ref "C9") (pin "1") (pinfunction "1_1") (pintype "passive"))
      (node (ref "D1") (pin "A") (pinfunction "A_A") (pintype "passive"))
      (node (ref "D2") (pin "A") (pinfunction "A_A") (pintype "passive"))
      (node (ref "D3") (pin "A") (pinfunction "A_A") (pintype "passive"))
      (node (ref "F") (pin "2") (pinfunction "2_2") (pintype "bidirectional"))
      (node (ref "HOLDR") (pin "2") (pinfunction "2_2") (pintype "passive"))
      (node (ref "IC1") (pin "8") (pinfunction "VDD_8") (pintype "power_in"))
      (node (ref "J1") (pin "4") (pinfunction "VDD_4") (pintype "bidirectional"))
      (node (ref "J2") (pin "5") (pinfunction "5_5") (pintype "passive"))
      (node (ref "J3") (pin "1") (pinfunction "1_1") (pintype "passive"))
      (node (ref "J4") (pin "2") (pinfunction "2_2") (pintype "bidirectional"))
      (node (ref "L2") (pin "1") (pinfunction "1_1") (pintype "passive"))
      (node (ref "LPS-1") (pin "1") (pinfunction "VCCIO_1") (pintype "bidirectional"))
      (node (ref "LPS-1") (pin "10") (pinfunction "VCC_10") (pintype "bidirectional"))
      (node (ref "LPS-1") (pin "6") (pinfunction "CS_6") (pintype "bidirectional"))
      (node (ref "LPSC1") (pin "1") (pinfunction "1_1") (pintype "passive"))
      (node (ref "LPSC2") (pin "1") (pinfunction "1_1") (pintype "passive"))
      (node (ref "MS5611") (pin "1") (pinfunction "1_1") (pintype "passive"))
      (node (ref "R10") (pin "2") (pinfunction "2_2") (pintype "passive"))
      (node (ref "R14") (pin "2") (pinfunction "2_2") (pintype "passive"))
      (node (ref "R15") (pin "2") (pinfunction "2_2") (pintype "passive"))
      (node (ref "R16") (pin "2") (pinfunction "2_2") (pintype "passive"))
      (node (ref "R2") (pin "2") (pinfunction "2_2") (pintype "passive"))
      (node (ref "R3") (pin "1") (pinfunction "1_1") (pintype "passive"))
      (node (ref "R4") (pin "2") (pinfunction "2_2") (pintype "passive"))
      (node (ref "R5") (pin "1") (pinfunction "1_1") (pintype "passive"))
      (node (ref "R6") (pin "2") (pinfunction "2_2") (pintype "passive"))
      (node (ref "R7") (pin "2") (pinfunction "2_2") (pintype "passive"))
      (node (ref "RD") (pin "A") (pinfunction "A_A") (pintype "passive"))
      (node (ref "U1") (pin "14") (pinfunction "VDD2_14") (pintype "power_in"))
      (node (ref "U1") (pin "17") (pinfunction "VDD1_17") (pintype "power_in"))
      (node (ref "U2") (pin "14") (pinfunction "VDD2_14") (pintype "power_in"))
      (node (ref "U2") (pin "17") (pinfunction "VDD1_17") (pintype "power_in"))
      (node (ref "U3") (pin "2") (pinfunction "CSB_2") (pintype "input"))
      (node (ref "U3") (pin "6") (pinfunction "VDDIO_6") (pintype "power_in"))
      (node (ref "U3") (pin "8") (pinfunction "VDD_8") (pintype "power_in"))
      (node (ref "U4") (pin "14") (pinfunction "VDD2_14") (pintype "power_in"))
      (node (ref "U4") (pin "17") (pinfunction "VDD1_17") (pintype "power_in"))
      (node (ref "U6") (pin "3") (pinfunction "~{WP(D2})_3") (pintype "bidirectional"))
      (node (ref "U6") (pin "7") (pinfunction "~{HOLD(D3})_7") (pintype "bidirectional"))
      (node (ref "U6") (pin "8") (pinfunction "VCC_8") (pintype "bidirectional"))
      (node (ref "U7") (pin "1") (pinfunction "VDD_1") (pintype "power_in"))
      (node (ref "U7") (pin "2") (pinfunction "PS_2") (pintype "input"))
      (node (ref "U8") (pin "1") (pinfunction "VBAT_1") (pintype "power_in"))
      (node (ref "U8") (pin "24") (pinfunction "VDD_1_24") (pintype "power_in"))
      (node (ref "U8") (pin "36") (pinfunction "VDD_2_36") (pintype "power_in"))
      (node (ref "U8") (pin "48") (pinfunction "VDD_3_48") (pintype "power_in"))
      (node (ref "X1") (pin "4") (pinfunction "S_4") (pintype "passive"))
    )
    (net (code "2") (name "BT0") (class "Default")
      (node (ref "R1") (pin "2") (pinfunction "2_2") (pintype "passive"))
      (node (ref "U8") (pin "44") (pinfunction "BOOT0_44") (pintype "input"))
    )
    (net (code "3") (name "BUZZER") (class "Default")
      (node (ref "BUZ") (pin "1") (pinfunction "1_1") (pintype "passive"))
      (node (ref "U8") (pin "18") (pinfunction "PB0_18") (pintype "bidirectional"))
    )
    (net (code "4") (name "CMISO") (class "Default")
      (node (ref "J4") (pin "1") (pinfunction "1_1") (pintype "bidirectional"))
      (node (ref "U4") (pin "5") (pinfunction "MISO_5") (pintype "bidirectional"))
      (node (ref "U6") (pin "2") (pinfunction "SO(D1)_2") (pintype "bidirectional"))
    )
    (net (code "5") (name "CMOSI") (class "Default")
      (node (ref "J4") (pin "4") (pinfunction "4_4") (pintype "bidirectional"))
      (node (ref "U4") (pin "4") (pinfunction "MOSI_4") (pintype "bidirectional"))
      (node (ref "U6") (pin "5") (pinfunction "SI(D0)_5") (pintype "bidirectional"))
    )
    (net (code "6") (name "CS") (class "Default")
      (node (ref "J1") (pin "2") (pinfunction "CD/DAT3(~{CS})_2") (pintype "bidirectional"))
      (node (ref "U8") (pin "29") (pinfunction "PA8_29") (pintype "bidirectional"))
    )
    (net (code "7") (name "CSCK") (class "Default")
      (node (ref "J4") (pin "3") (pinfunction "3_3") (pintype "bidirectional"))
      (node (ref "U4") (pin "3") (pinfunction "SCK_3") (pintype "output"))
      (node (ref "U6") (pin "6") (pinfunction "SCK_6") (pintype "bidirectional"))
    )
    (net (code "8") (name "CSF") (class "Default")
      (node (ref "IC1") (pin "1") (pinfunction "R_1") (pintype "open_collector"))
      (node (ref "U8") (pin "25") (pinfunction "PB12_25") (pintype "bidirectional"))
    )
    (net (code "9") (name "CSN_EE") (class "Default")
      (node (ref "J4") (pin "5") (pinfunction "5_5") (pintype "bidirectional"))
      (node (ref "U4") (pin "6") (pinfunction "CSN_6") (pintype "output"))
      (node (ref "U6") (pin "1") (pinfunction "~{CS}_1") (pintype "bidirectional"))
    )
    (net (code "10") (name "DRDY") (class "Default")
      (node (ref "J2") (pin "1") (pinfunction "1_1") (pintype "passive"))
      (node (ref "U8") (pin "2") (pinfunction "PC13_2") (pintype "bidirectional"))
    )
    (net (code "11") (name "GND") (class "Default")
      (node (ref "C1") (pin "2") (pinfunction "2_2") (pintype "passive"))
      (node (ref "C11") (pin "1") (pinfunction "1_1") (pintype "passive"))
      (node (ref "C12") (pin "1") (pinfunction "1_1") (pintype "passive"))
      (node (ref "C14") (pin "1") (pinfunction "1_1") (pintype "passive"))
      (node (ref "C15") (pin "1") (pinfunction "1_1") (pintype "passive"))
      (node (ref "C16") (pin "1") (pinfunction "1_1") (pintype "passive"))
      (node (ref "C17") (pin "1") (pinfunction "1_1") (pintype "passive"))
      (node (ref "C2") (pin "2") (pinfunction "2_2") (pintype "passive"))
      (node (ref "C3") (pin "2") (pinfunction "2_2") (pintype "passive"))
      (node (ref "C4") (pin "1") (pinfunction "1_1") (pintype "passive"))
      (node (ref "C5") (pin "1") (pinfunction "1_1") (pintype "passive"))
      (node (ref "C6") (pin "2") (pinfunction "2_2") (pintype "passive"))
      (node (ref "C7") (pin "2") (pinfunction "2_2") (pintype "passive"))
      (node (ref "C8") (pin "2") (pinfunction "2_2") (pintype "passive"))
      (node (ref "C9") (pin "2") (pinfunction "2_2") (pintype "passive"))
      (node (ref "IC1") (pin "4") (pinfunction "GND_4") (pintype "power_in"))
      (node (ref "J1") (pin "6") (pinfunction "VSS_6") (pintype "bidirectional"))
      (node (ref "J2") (pin "4") (pinfunction "4_4") (pintype "passive"))
      (node (ref "J3") (pin "4") (pinfunction "4_4") (pintype "passive"))
      (node (ref "J4") (pin "6") (pinfunction "6_6") (pintype "bidirectional"))
      (node (ref "J5") (pin "GND1") (pinfunction "GND_GND1") (pintype "power_in"))
      (node (ref "J5") (pin "SHLD1") (pinfunction "SHIELD_SHLD1") (pintype "bidirectional"))
      (node (ref "J5") (pin "SHLD2") (pinfunction "SHIELD_SHLD2") (pintype "bidirectional"))
      (node (ref "J5") (pin "SHLD3") (pinfunction "SHIELD_SHLD3") (pintype "bidirectional"))
      (node (ref "LPS-1") (pin "3") (pinfunction "RES_3") (pintype "bidirectional"))
      (node (ref "LPS-1") (pin "5") (pinfunction "SDO/SAO_5") (pintype "bidirectional"))
      (node (ref "LPS-1") (pin "8") (pinfunction "GND_8") (pintype "bidirectional"))
      (node (ref "LPS-1") (pin "9") (pinfunction "GND_9") (pintype "bidirectional"))
      (node (ref "LPSC1") (pin "2") (pinfunction "2_2") (pintype "passive"))
      (node (ref "LPSC2") (pin "2") (pinfunction "2_2") (pintype "passive"))
      (node (ref "LS2") (pin "-") (pinfunction "2_-") (pintype "passive"))
      (node (ref "MS5611") (pin "2") (pinfunction "2_2") (pintype "passive"))
      (node (ref "OSCC1") (pin "2") (pinfunction "2_2") (pintype "passive"))
      (node (ref "OSCC2") (pin "2") (pinfunction "2_2") (pintype "passive"))
      (node (ref "POWER1") (pin "1") (pinfunction "1_1") (pintype "passive"))
      (node (ref "R1") (pin "1") (pinfunction "1_1") (pintype "passive"))
      (node (ref "RC1") (pin "C") (pinfunction "-_C") (pintype "passive"))
      (node (ref "RC2") (pin "2") (pinfunction "2_2") (pintype "passive"))
      (node (ref "RC3") (pin "2") (pinfunction "2_2") (pintype "passive"))
      (node (ref "RC4") (pin "C") (pinfunction "-_C") (pintype "passive"))
      (node (ref "RRO") (pin "2") (pinfunction "2_2") (pintype "passive"))
      (node (ref "RRO1") (pin "2") (pinfunction "2_2") (pintype "passive"))
      (node (ref "SL1") (pin "1") (pinfunction "1_1") (pintype "passive"))
      (node (ref "U1") (pin "16") (pinfunction "GND_16") (pintype "power_in"))
      (node (ref "U2") (pin "16") (pinfunction "GND_16") (pintype "power_in"))
      (node (ref "U3") (pin "1") (pinfunction "GND_1") (pintype "power_in"))
      (node (ref "U3") (pin "5") (pinfunction "SDO_5") (pintype "bidirectional"))
      (node (ref "U3") (pin "7") (pinfunction "GND_7") (pintype "power_in"))
      (node (ref "U4") (pin "16") (pinfunction "GND_16") (pintype "power_in"))
      (node (ref "U4") (pin "8") (pinfunction "I2C_ENB_8") (pintype "input"))
      (node (ref "U5") (pin "1") (pinfunction "ADJ_1") (pintype "power_in"))
      (node (ref "U6") (pin "4") (pinfunction "GND_4") (pintype "bidirectional"))
      (node (ref "U7") (pin "3") (pinfunction "GND_3") (pintype "passive"))
      (node (ref "U7") (pin "4") (pinfunction "CSB_2_4") (pintype "input"))
      (node (ref "U7") (pin "5") (pinfunction "CSB_5") (pintype "input"))
      (node (ref "U8") (pin "23") (pinfunction "VSS_1_23") (pintype "power_in"))
      (node (ref "U8") (pin "35") (pinfunction "VSS_2_35") (pintype "power_in"))
      (node (ref "U8") (pin "47") (pinfunction "VSS_3_47") (pintype "power_in"))
      (node (ref "U8") (pin "8") (pinfunction "VSSA_8") (pintype "power_in"))
      (node (ref "VDDA1") (pin "2") (pinfunction "2_2") (pintype "passive"))
      (node (ref "VDDA2") (pin "2") (pinfunction "2_2") (pintype "passive"))
      (node (ref "WPR") (pin "1") (pinfunction "1_1") (pintype "passive"))
      (node (ref "X1") (pin "1") (pinfunction "S_1") (pintype "passive"))
      (node (ref "Y2") (pin "2") (pinfunction "GND_2") (pintype "passive"))
      (node (ref "Y2") (pin "4") (pinfunction "GND_4") (pintype "passive"))
    )
    (net (code "12") (name "HOLD") (class "Default")
      (node (ref "HOLDR") (pin "1") (pinfunction "1_1") (pintype "passive"))
      (node (ref "IC1") (pin "7") (pinfunction "SET_7") (pintype "input"))
      (node (ref "U8") (pin "31") (pinfunction "PA10_31") (pintype "bidirectional"))
    )
    (net (code "13") (name "HT") (class "Default")
      (node (ref "U5") (pin "4") (pinfunction "HT_4") (pintype "bidirectional"))
    )
    (net (code "14") (name "INT") (class "Default")
      (node (ref "U4") (pin "13") (pinfunction "INT_13") (pintype "output"))
      (node (ref "U8") (pin "39") (pinfunction "PB3_39") (pintype "bidirectional"))
    )
    (net (code "15") (name "INT1") (class "Default")
      (node (ref "LPS-1") (pin "7") (pinfunction "INT1_7") (pintype "bidirectional"))
      (node (ref "U8") (pin "40") (pinfunction "PB4_40") (pintype "bidirectional"))
    )
    (net (code "16") (name "LED") (class "Default")
      (node (ref "RD1") (pin "A") (pinfunction "A_A") (pintype "passive"))
      (node (ref "U8") (pin "17") (pinfunction "PA7_17") (pintype "bidirectional"))
    )
    (net (code "17") (name "MISO") (class "Default")
      (node (ref "IC1") (pin "2") (pinfunction "G_2") (pintype "open_collector"))
      (node (ref "J1") (pin "7") (pinfunction "DAT0(DO)_7") (pintype "bidirectional"))
      (node (ref "U8") (pin "27") (pinfunction "PB14_27") (pintype "bidirectional"))
    )
    (net (code "18") (name "MOSI") (class "Default")
      (node (ref "IC1") (pin "5") (pinfunction "DO_5") (pintype "output"))
      (node (ref "J1") (pin "3") (pinfunction "CMD(DI)_3") (pintype "bidirectional"))
      (node (ref "U8") (pin "28") (pinfunction "PB15_28") (pintype "bidirectional"))
    )
    (net (code "19") (name "NRST") (class "Default")
      (node (ref "C17") (pin "2") (pinfunction "2_2") (pintype "passive"))
      (node (ref "R2") (pin "1") (pinfunction "1_1") (pintype "passive"))
      (node (ref "U8") (pin "7") (pinfunction "NRST_7") (pintype "bidirectional"))
    )
    (net (code "20") (name "Net-(LS2-1)") (class "Default")
      (node (ref "BUZ") (pin "2") (pinfunction "2_2") (pintype "passive"))
      (node (ref "LS2") (pin "+") (pinfunction "1_+") (pintype "passive"))
    )
    (net (code "21") (name "Net-(POWER1-Pad2)") (class "Default")
      (node (ref "POWER1") (pin "2") (pinfunction "2_2") (pintype "passive"))
      (node (ref "SW1") (pin "1") (pinfunction "1_1") (pintype "passive"))
    )
    (net (code "22") (name "Net-(RC1-+)") (class "Default")
      (node (ref "RC1") (pin "A") (pinfunction "+_A") (pintype "passive"))
      (node (ref "RC2") (pin "1") (pinfunction "1_1") (pintype "passive"))
      (node (ref "RGD") (pin "C") (pinfunction "C_C") (pintype "passive"))
      (node (ref "U5") (pin "3") (pinfunction "VIN_3") (pintype "input"))
    )
    (net (code "23") (name "Net-(RC4-+)") (class "Default")
      (node (ref "F") (pin "1") (pinfunction "1_1") (pintype "bidirectional"))
      (node (ref "RC3") (pin "1") (pinfunction "1_1") (pintype "passive"))
      (node (ref "RC4") (pin "A") (pinfunction "+_A") (pintype "passive"))
      (node (ref "U5") (pin "2") (pinfunction "VOUT_2") (pintype "output"))
    )
    (net (code "24") (name "Net-(RD-PadC)") (class "Default")
      (node (ref "RD") (pin "C") (pinfunction "C_C") (pintype "passive"))
      (node (ref "RRO") (pin "1") (pinfunction "1_1") (pintype "passive"))
    )
    (net (code "25") (name "Net-(RD1-PadC)") (class "Default")
      (node (ref "RD1") (pin "C") (pinfunction "C_C") (pintype "passive"))
      (node (ref "RRO1") (pin "1") (pinfunction "1_1") (pintype "passive"))
    )
    (net (code "26") (name "Net-(U1-I2C_ENB)") (class "Default")
      (node (ref "R3") (pin "2") (pinfunction "2_2") (pintype "passive"))
      (node (ref "U1") (pin "8") (pinfunction "I2C_ENB_8") (pintype "input"))
    )
    (net (code "27") (name "Net-(U1-LED_IND)") (class "Default")
      (node (ref "D2") (pin "C") (pinfunction "C_C") (pintype "passive"))
      (node (ref "U1") (pin "18") (pinfunction "LED_IND_18") (pintype "output"))
    )
    (net (code "28") (name "Net-(U2-I2C_ENB)") (class "Default")
      (node (ref "R5") (pin "2") (pinfunction "2_2") (pintype "passive"))
      (node (ref "U2") (pin "8") (pinfunction "I2C_ENB_8") (pintype "input"))
    )
    (net (code "29") (name "Net-(U2-LED_IND)") (class "Default")
      (node (ref "D3") (pin "C") (pinfunction "C_C") (pintype "passive"))
      (node (ref "U2") (pin "18") (pinfunction "LED_IND_18") (pintype "output"))
    )
    (net (code "30") (name "Net-(U4-LED_IND)") (class "Default")
      (node (ref "D1") (pin "C") (pinfunction "C_C") (pintype "passive"))
      (node (ref "U4") (pin "18") (pinfunction "LED_IND_18") (pintype "output"))
    )
    (net (code "31") (name "OSC_IN") (class "Default")
      (node (ref "OSCC1") (pin "1") (pinfunction "1_1") (pintype "passive"))
      (node (ref "U8") (pin "5") (pinfunction "OSC_IN_5") (pintype "input"))
      (node (ref "Y2") (pin "1") (pinfunction "1_1") (pintype "passive"))
    )
    (net (code "32") (name "OSC_OUT") (class "Default")
      (node (ref "OSCC2") (pin "1") (pinfunction "1_1") (pintype "passive"))
      (node (ref "U8") (pin "6") (pinfunction "OSC_OUT_6") (pintype "output"))
      (node (ref "Y2") (pin "3") (pinfunction "3_3") (pintype "passive"))
    )
    (net (code "33") (name "RESN") (class "Default")
      (node (ref "R7") (pin "1") (pinfunction "1_1") (pintype "passive"))
      (node (ref "SL1") (pin "2") (pinfunction "2_2") (pintype "passive"))
      (node (ref "U4") (pin "2") (pinfunction "RESN_2") (pintype "input"))
    )
    (net (code "34") (name "RX1") (class "Default")
      (node (ref "U4") (pin "12") (pinfunction "TX/SDA_S_12") (pintype "bidirectional"))
      (node (ref "U8") (pin "43") (pinfunction "PB7_43") (pintype "bidirectional"))
    )
    (net (code "35") (name "RX2") (class "Default")
      (node (ref "U8") (pin "13") (pinfunction "PA3_13") (pintype "bidirectional"))
      (node (ref "X1") (pin "3") (pinfunction "S_3") (pintype "passive"))
    )
    (net (code "36") (name "SCK") (class "Default")
      (node (ref "IC1") (pin "6") (pinfunction "DIN_6") (pintype "input"))
      (node (ref "J1") (pin "5") (pinfunction "CLK(SCK)_5") (pintype "bidirectional"))
      (node (ref "U8") (pin "26") (pinfunction "PB13_26") (pintype "bidirectional"))
    )
    (net (code "37") (name "SCL") (class "Default")
      (node (ref "J2") (pin "3") (pinfunction "3_3") (pintype "passive"))
      (node (ref "LPS-1") (pin "2") (pinfunction "SCL/SPC_2") (pintype "bidirectional"))
      (node (ref "R4") (pin "1") (pinfunction "1_1") (pintype "passive"))
      (node (ref "U3") (pin "4") (pinfunction "SCK_4") (pintype "input"))
      (node (ref "U7") (pin "8") (pinfunction "SCLK_8") (pintype "input"))
      (node (ref "U8") (pin "45") (pinfunction "PB8_45") (pintype "bidirectional"))
    )
    (net (code "38") (name "SCL_M") (class "Default")
      (node (ref "R15") (pin "1") (pinfunction "1_1") (pintype "passive"))
      (node (ref "U1") (pin "9") (pinfunction "SCL_M_9") (pintype "output"))
      (node (ref "U2") (pin "9") (pinfunction "SCL_M_9") (pintype "output"))
      (node (ref "U4") (pin "9") (pinfunction "SCL_M_9") (pintype "output"))
    )
    (net (code "39") (name "SDA") (class "Default")
      (node (ref "J2") (pin "2") (pinfunction "2_2") (pintype "passive"))
      (node (ref "LPS-1") (pin "4") (pinfunction "SDA/SDI/SDO_4") (pintype "bidirectional"))
      (node (ref "R6") (pin "1") (pinfunction "1_1") (pintype "passive"))
      (node (ref "U3") (pin "3") (pinfunction "SDI_3") (pintype "bidirectional"))
      (node (ref "U7") (pin "7") (pinfunction "SDI/SDA_7") (pintype "bidirectional"))
      (node (ref "U8") (pin "46") (pinfunction "PB9_46") (pintype "bidirectional"))
    )
    (net (code "40") (name "SDA_M") (class "Default")
      (node (ref "R16") (pin "1") (pinfunction "1_1") (pintype "passive"))
      (node (ref "U1") (pin "10") (pinfunction "SDA_M_10") (pintype "bidirectional"))
      (node (ref "U2") (pin "10") (pinfunction "SDA_M_10") (pintype "bidirectional"))
      (node (ref "U4") (pin "10") (pinfunction "SDA_M_10") (pintype "bidirectional"))
    )
    (net (code "41") (name "SLV1_R") (class "Default")
      (node (ref "R14") (pin "1") (pinfunction "1_1") (pintype "passive"))
      (node (ref "U1") (pin "2") (pinfunction "RESN_2") (pintype "input"))
      (node (ref "U4") (pin "1") (pinfunction "SLV1_RESN_1") (pintype "bidirectional"))
    )
    (net (code "42") (name "SLV2_R") (class "Default")
      (node (ref "R10") (pin "1") (pinfunction "1_1") (pintype "passive"))
      (node (ref "U2") (pin "2") (pinfunction "RESN_2") (pintype "input"))
      (node (ref "U4") (pin "20") (pinfunction "SLV2_RESN_20") (pintype "output"))
    )
    (net (code "43") (name "SWCLK") (class "Default")
      (node (ref "J3") (pin "3") (pinfunction "3_3") (pintype "passive"))
      (node (ref "U8") (pin "37") (pinfunction "PA14_37") (pintype "bidirectional"))
    )
    (net (code "44") (name "SWDIO") (class "Default")
      (node (ref "J3") (pin "2") (pinfunction "2_2") (pintype "passive"))
      (node (ref "U8") (pin "34") (pinfunction "PA13_34") (pintype "bidirectional"))
    )
    (net (code "45") (name "TX1") (class "Default")
      (node (ref "U4") (pin "11") (pinfunction "RX/SCL_S_11") (pintype "bidirectional"))
      (node (ref "U8") (pin "42") (pinfunction "PB6_42") (pintype "bidirectional"))
    )
    (net (code "46") (name "TX2") (class "Default")
      (node (ref "U8") (pin "12") (pinfunction "PA2_12") (pintype "bidirectional"))
      (node (ref "X1") (pin "2") (pinfunction "S_2") (pintype "passive"))
    )
    (net (code "47") (name "USB_N") (class "Default")
      (node (ref "J5") (pin "D-1") (pinfunction "D-_D-1") (pintype "bidirectional"))
      (node (ref "U8") (pin "32") (pinfunction "PA11_32") (pintype "bidirectional"))
    )
    (net (code "48") (name "USB_P") (class "Default")
      (node (ref "J5") (pin "D+1") (pinfunction "D+_D+1") (pintype "bidirectional"))
      (node (ref "U8") (pin "33") (pinfunction "PA12_33") (pintype "bidirectional"))
    )
    (net (code "49") (name "VDDA") (class "Default")
      (node (ref "L2") (pin "2") (pinfunction "2_2") (pintype "passive"))
      (node (ref "U8") (pin "9") (pinfunction "VDDA_9") (pintype "power_in"))
      (node (ref "VDDA1") (pin "1") (pinfunction "1_1") (pintype "passive"))
      (node (ref "VDDA2") (pin "1") (pinfunction "1_1") (pintype "passive"))
    )
    (net (code "50") (name "VIN") (class "Default")
      (node (ref "J5") (pin "VBUS1") (pinfunction "VBUS_VBUS1") (pintype "power_in"))
      (node (ref "RGD") (pin "A") (pinfunction "A_A") (pintype "passive"))
      (node (ref "SW1") (pin "2") (pinfunction "2_2") (pintype "passive"))
    )
    (net (code "51") (name "WP") (class "Default")
      (node (ref "IC1") (pin "3") (pinfunction "B_3") (pintype "open_collector"))
      (node (ref "U8") (pin "30") (pinfunction "PA9_30") (pintype "bidirectional"))
      (node (ref "WPR") (pin "2") (pinfunction "2_2") (pintype "passive"))
    )
    (net (code "52") (name "unconnected-(J1B-DAT1(RSV)-Pad8)") (class "Default")
      (node (ref "J1") (pin "8") (pinfunction "DAT1(RSV)_8") (pintype "bidirectional"))
    )
    (net (code "53") (name "unconnected-(J1B-DAT2(NC)-Pad1)") (class "Default")
      (node (ref "J1") (pin "1") (pinfunction "DAT2(NC)_1") (pintype "bidirectional"))
    )
    (net (code "54") (name "unconnected-(J5-USBID-PadID1)") (class "Default")
      (node (ref "J5") (pin "ID1") (pinfunction "USBID_ID1") (pintype "bidirectional"))
    )
    (net (code "55") (name "unconnected-(U1-CSN-Pad6)") (class "Default")
      (node (ref "U1") (pin "6") (pinfunction "CSN_6") (pintype "output"))
    )
    (net (code "56") (name "unconnected-(U1-INT-Pad13)") (class "Default")
      (node (ref "U1") (pin "13") (pinfunction "INT_13") (pintype "output"))
    )
    (net (code "57") (name "unconnected-(U1-LED_DRV-Pad15)") (class "Default")
      (node (ref "U1") (pin "15") (pinfunction "LED_DRV_15") (pintype "output"))
    )
    (net (code "58") (name "unconnected-(U1-MISO-Pad5)") (class "Default")
      (node (ref "U1") (pin "5") (pinfunction "MISO_5") (pintype "bidirectional"))
    )
    (net (code "59") (name "unconnected-(U1-MOSI-Pad4)") (class "Default")
      (node (ref "U1") (pin "4") (pinfunction "MOSI_4") (pintype "bidirectional"))
    )
    (net (code "60") (name "unconnected-(U1-RX{slash}SCL_S-Pad11)") (class "Default")
      (node (ref "U1") (pin "11") (pinfunction "RX/SCL_S_11") (pintype "bidirectional"))
    )
    (net (code "61") (name "unconnected-(U1-SCK-Pad3)") (class "Default")
      (node (ref "U1") (pin "3") (pinfunction "SCK_3") (pintype "output"))
    )
    (net (code "62") (name "unconnected-(U1-SLV1_RESN-Pad1)") (class "Default")
      (node (ref "U1") (pin "1") (pinfunction "SLV1_RESN_1") (pintype "bidirectional"))
    )
    (net (code "63") (name "unconnected-(U1-SLV2_RESN-Pad20)") (class "Default")
      (node (ref "U1") (pin "20") (pinfunction "SLV2_RESN_20") (pintype "output"))
    )
    (net (code "64") (name "unconnected-(U1-TX{slash}SDA_S-Pad12)") (class "Default")
      (node (ref "U1") (pin "12") (pinfunction "TX/SDA_S_12") (pintype "bidirectional"))
    )
    (net (code "65") (name "unconnected-(U2-CSN-Pad6)") (class "Default")
      (node (ref "U2") (pin "6") (pinfunction "CSN_6") (pintype "output"))
    )
    (net (code "66") (name "unconnected-(U2-INT-Pad13)") (class "Default")
      (node (ref "U2") (pin "13") (pinfunction "INT_13") (pintype "output"))
    )
    (net (code "67") (name "unconnected-(U2-LED_DRV-Pad15)") (class "Default")
      (node (ref "U2") (pin "15") (pinfunction "LED_DRV_15") (pintype "output"))
    )
    (net (code "68") (name "unconnected-(U2-MISO-Pad5)") (class "Default")
      (node (ref "U2") (pin "5") (pinfunction "MISO_5") (pintype "bidirectional"))
    )
    (net (code "69") (name "unconnected-(U2-MOSI-Pad4)") (class "Default")
      (node (ref "U2") (pin "4") (pinfunction "MOSI_4") (pintype "bidirectional"))
    )
    (net (code "70") (name "unconnected-(U2-RX{slash}SCL_S-Pad11)") (class "Default")
      (node (ref "U2") (pin "11") (pinfunction "RX/SCL_S_11") (pintype "bidirectional"))
    )
    (net (code "71") (name "unconnected-(U2-SCK-Pad3)") (class "Default")
      (node (ref "U2") (pin "3") (pinfunction "SCK_3") (pintype "output"))
    )
    (net (code "72") (name "unconnected-(U2-SLV1_RESN-Pad1)") (class "Default")
      (node (ref "U2") (pin "1") (pinfunction "SLV1_RESN_1") (pintype "bidirectional"))
    )
    (net (code "73") (name "unconnected-(U2-SLV2_RESN-Pad20)") (class "Default")
      (node (ref "U2") (pin "20") (pinfunction "SLV2_RESN_20") (pintype "output"))
    )
    (net (code "74") (name "unconnected-(U2-TX{slash}SDA_S-Pad12)") (class "Default")
      (node (ref "U2") (pin "12") (pinfunction "TX/SDA_S_12") (pintype "bidirectional"))
    )
    (net (code "75") (name "unconnected-(U4-LED_DRV-Pad15)") (class "Default")
      (node (ref "U4") (pin "15") (pinfunction "LED_DRV_15") (pintype "output"))
    )
    (net (code "76") (name "unconnected-(U7-SDO-Pad6)") (class "Default")
      (node (ref "U7") (pin "6") (pinfunction "SDO_6") (pintype "output"))
    )
    (net (code "77") (name "unconnected-(U8A-PA0-WKUP-Pad10)") (class "Default")
      (node (ref "U8") (pin "10") (pinfunction "PA0-WKUP_10") (pintype "bidirectional"))
    )
    (net (code "78") (name "unconnected-(U8A-PA1-Pad11)") (class "Default")
      (node (ref "U8") (pin "11") (pinfunction "PA1_11") (pintype "bidirectional"))
    )
    (net (code "79") (name "unconnected-(U8A-PA4-Pad14)") (class "Default")
      (node (ref "U8") (pin "14") (pinfunction "PA4_14") (pintype "bidirectional"))
    )
    (net (code "80") (name "unconnected-(U8A-PA5-Pad15)") (class "Default")
      (node (ref "U8") (pin "15") (pinfunction "PA5_15") (pintype "bidirectional"))
    )
    (net (code "81") (name "unconnected-(U8A-PA6-Pad16)") (class "Default")
      (node (ref "U8") (pin "16") (pinfunction "PA6_16") (pintype "bidirectional"))
    )
    (net (code "82") (name "unconnected-(U8A-PA15-Pad38)") (class "Default")
      (node (ref "U8") (pin "38") (pinfunction "PA15_38") (pintype "bidirectional"))
    )
    (net (code "83") (name "unconnected-(U8A-PB1-Pad19)") (class "Default")
      (node (ref "U8") (pin "19") (pinfunction "PB1_19") (pintype "bidirectional"))
    )
    (net (code "84") (name "unconnected-(U8A-PB2-Pad20)") (class "Default")
      (node (ref "U8") (pin "20") (pinfunction "PB2_20") (pintype "bidirectional"))
    )
    (net (code "85") (name "unconnected-(U8A-PB5-Pad41)") (class "Default")
      (node (ref "U8") (pin "41") (pinfunction "PB5_41") (pintype "bidirectional"))
    )
    (net (code "86") (name "unconnected-(U8A-PB10-Pad21)") (class "Default")
      (node (ref "U8") (pin "21") (pinfunction "PB10_21") (pintype "bidirectional"))
    )
    (net (code "87") (name "unconnected-(U8A-PB11-Pad22)") (class "Default")
      (node (ref "U8") (pin "22") (pinfunction "PB11_22") (pintype "bidirectional"))
    )
    (net (code "88") (name "unconnected-(U8A-PC14-OSC32_IN-Pad3)") (class "Default")
      (node (ref "U8") (pin "3") (pinfunction "PC14-OSC32_IN_3") (pintype "bidirectional"))
    )
    (net (code "89") (name "unconnected-(U8A-PC15-OSC32_OUT-Pad4)") (class "Default")
      (node (ref "U8") (pin "4") (pinfunction "PC15-OSC32_OUT_4") (pintype "bidirectional"))
    )
  )
)
